# CN-Cape006-via08-fixed.net
KiCad netlist of a schematic drawn in EAGLE
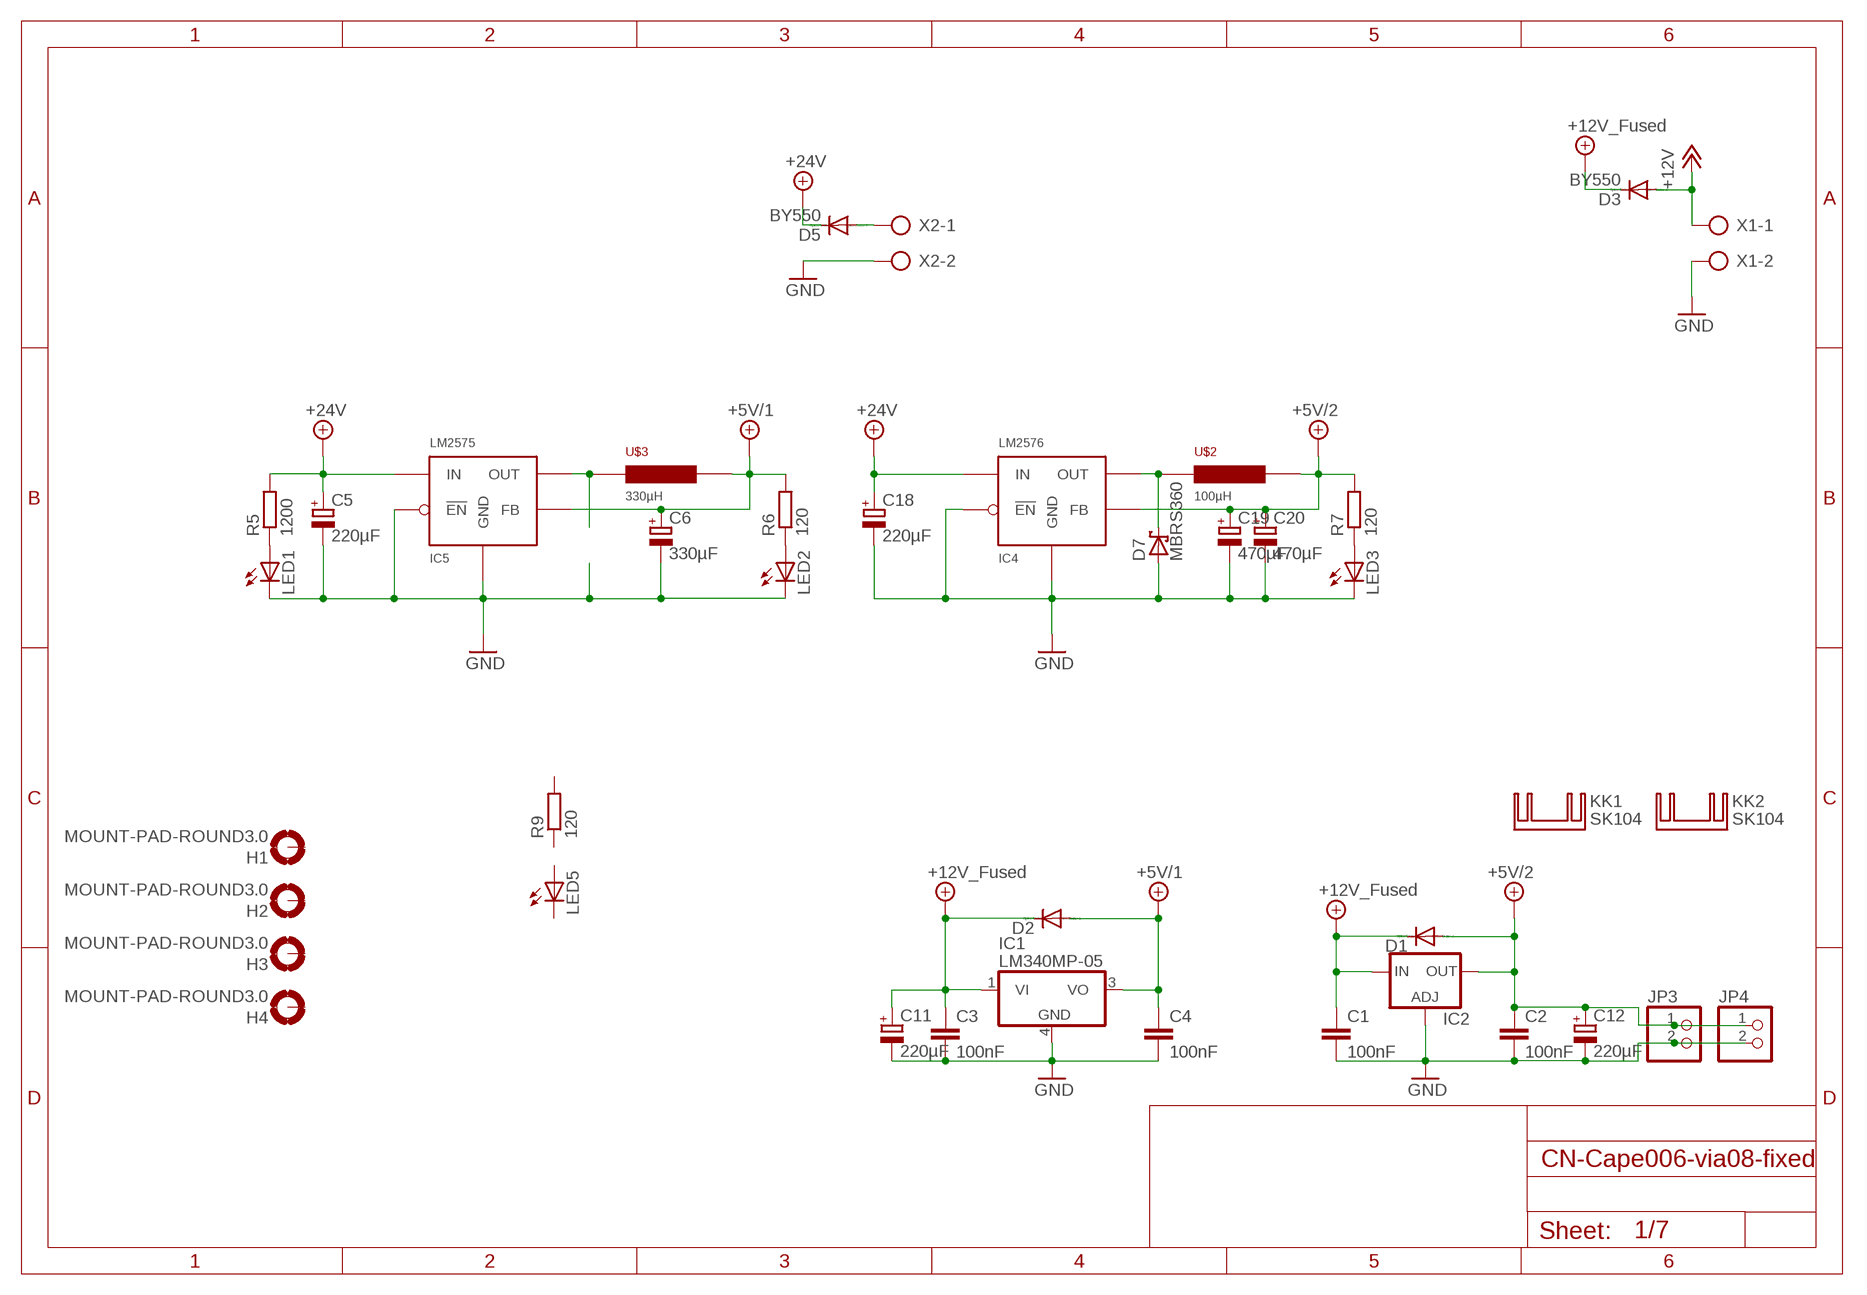
[diagram p0: schematic, sheet 1]
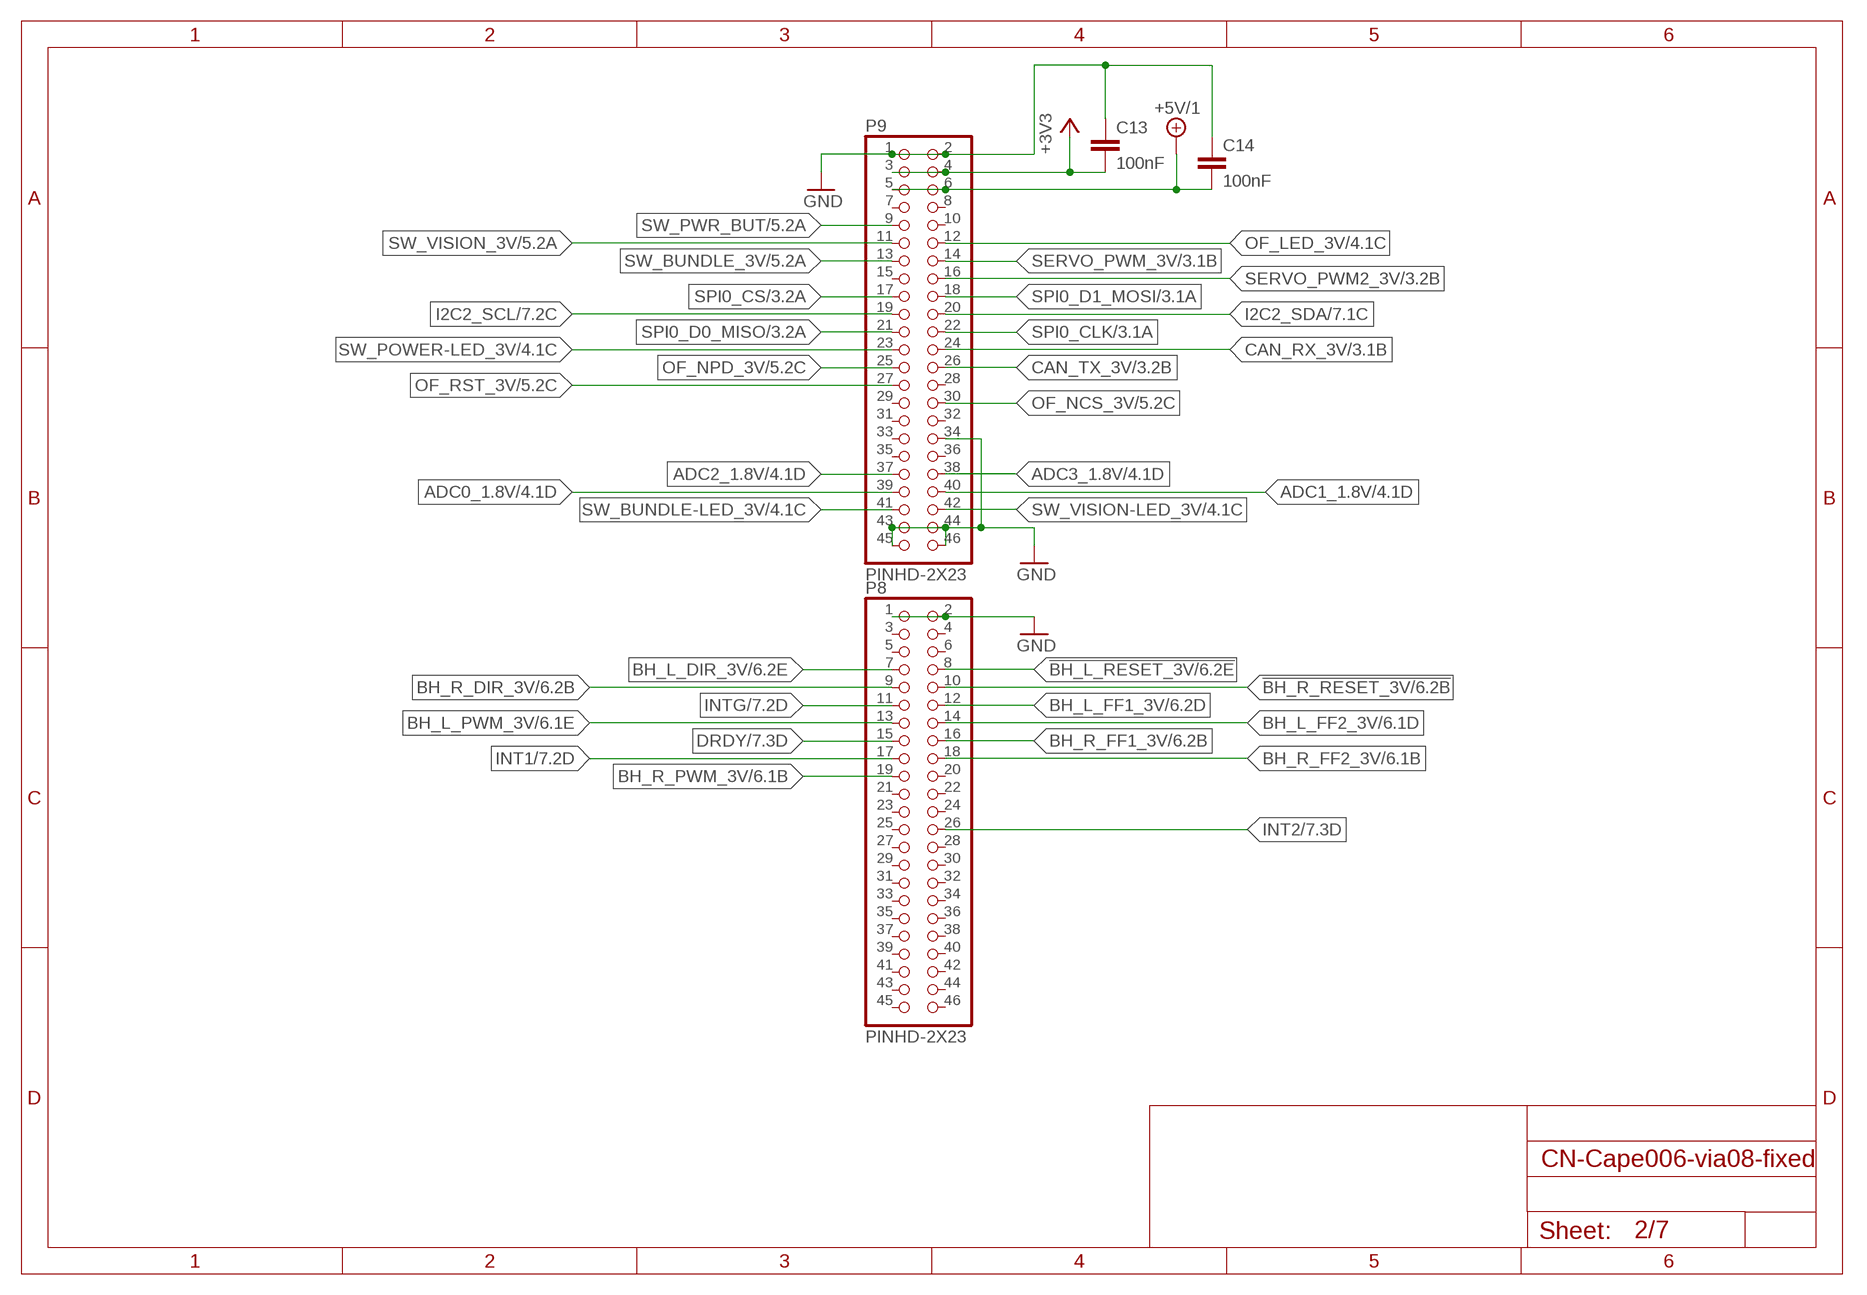
[diagram p1: schematic, sheet 2]
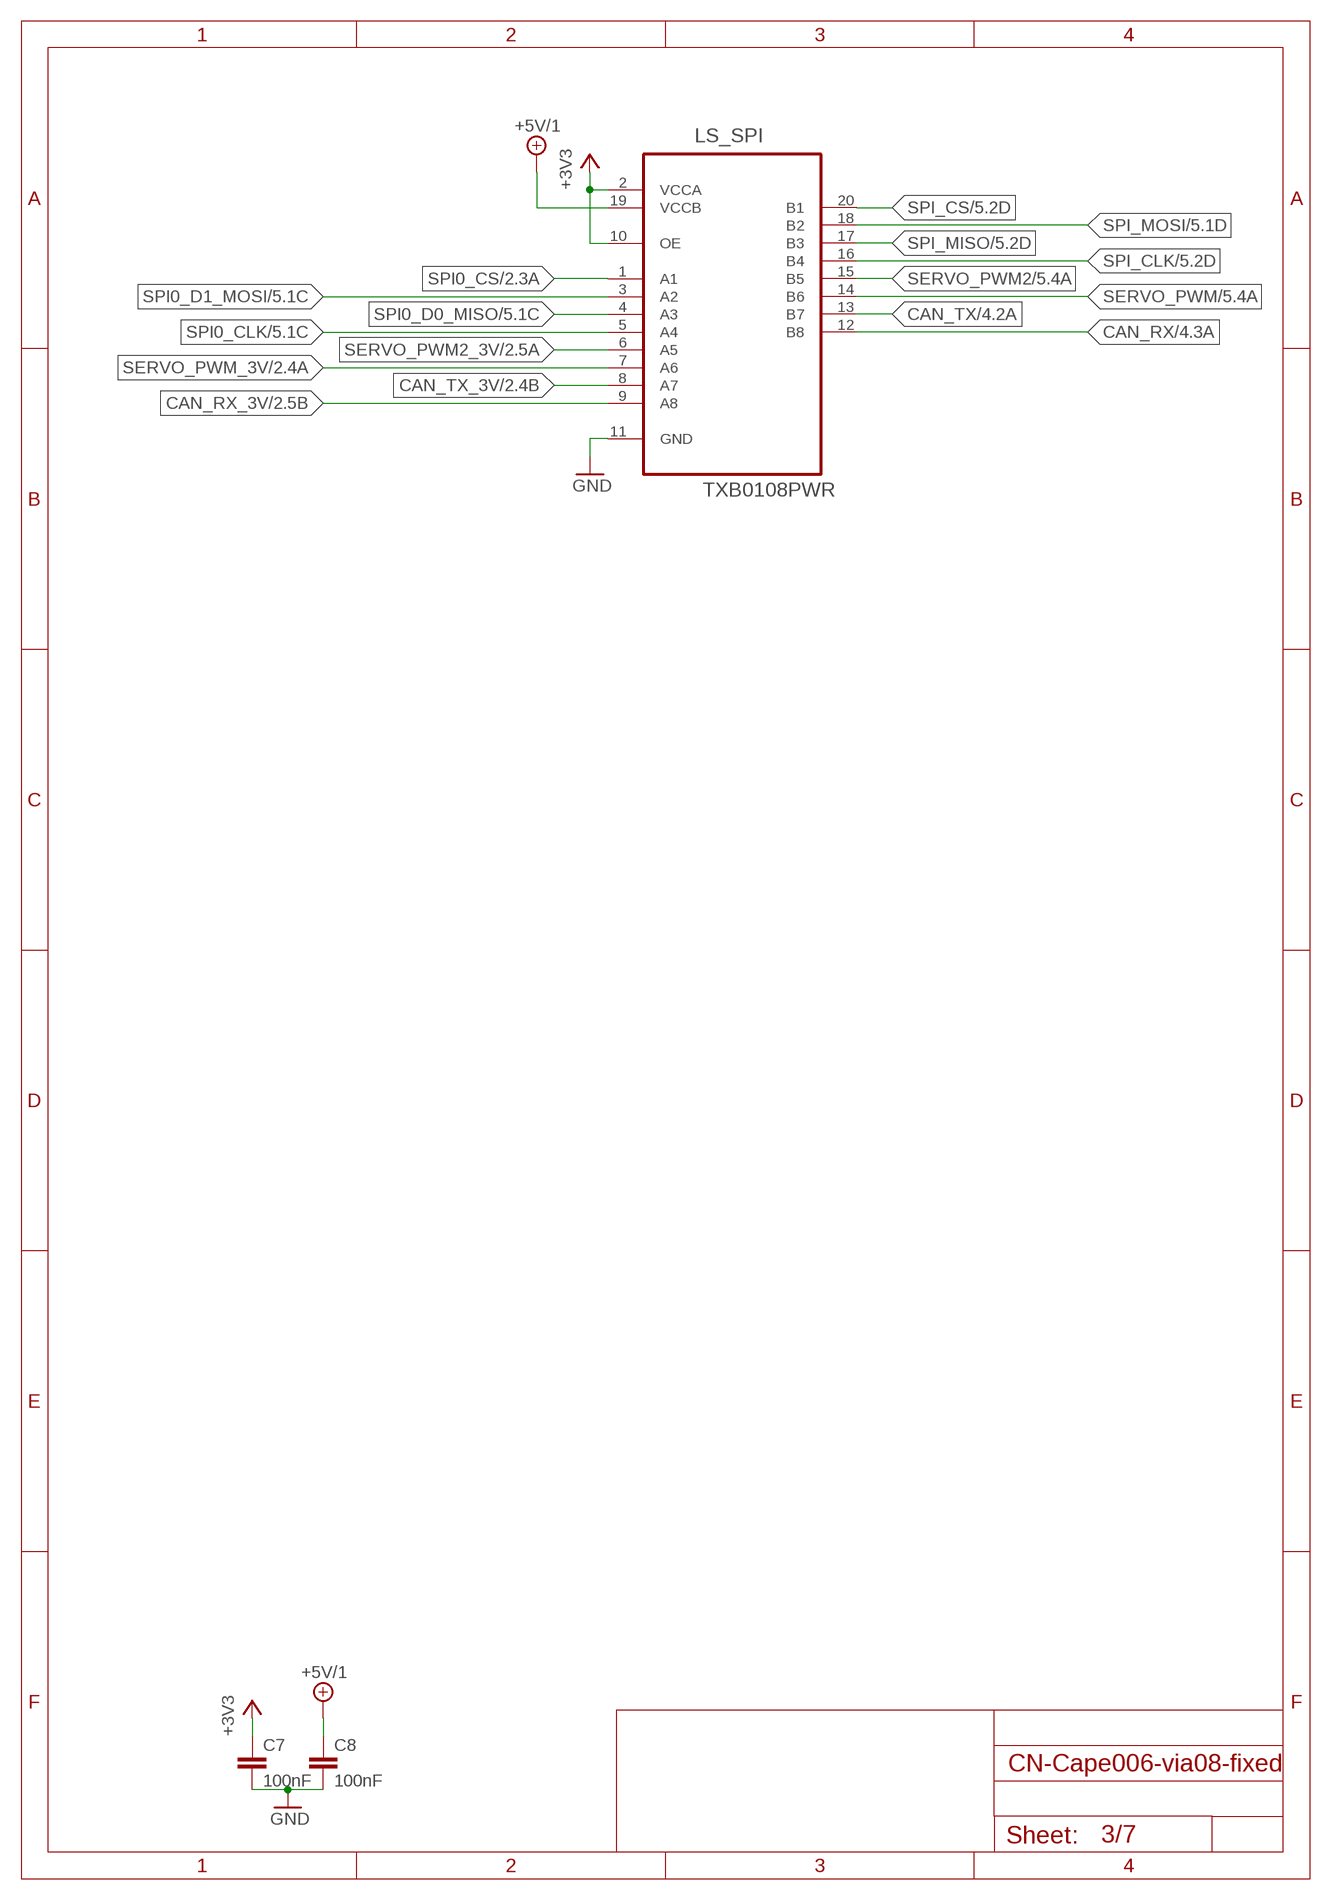
[diagram p2: schematic, sheet 3]
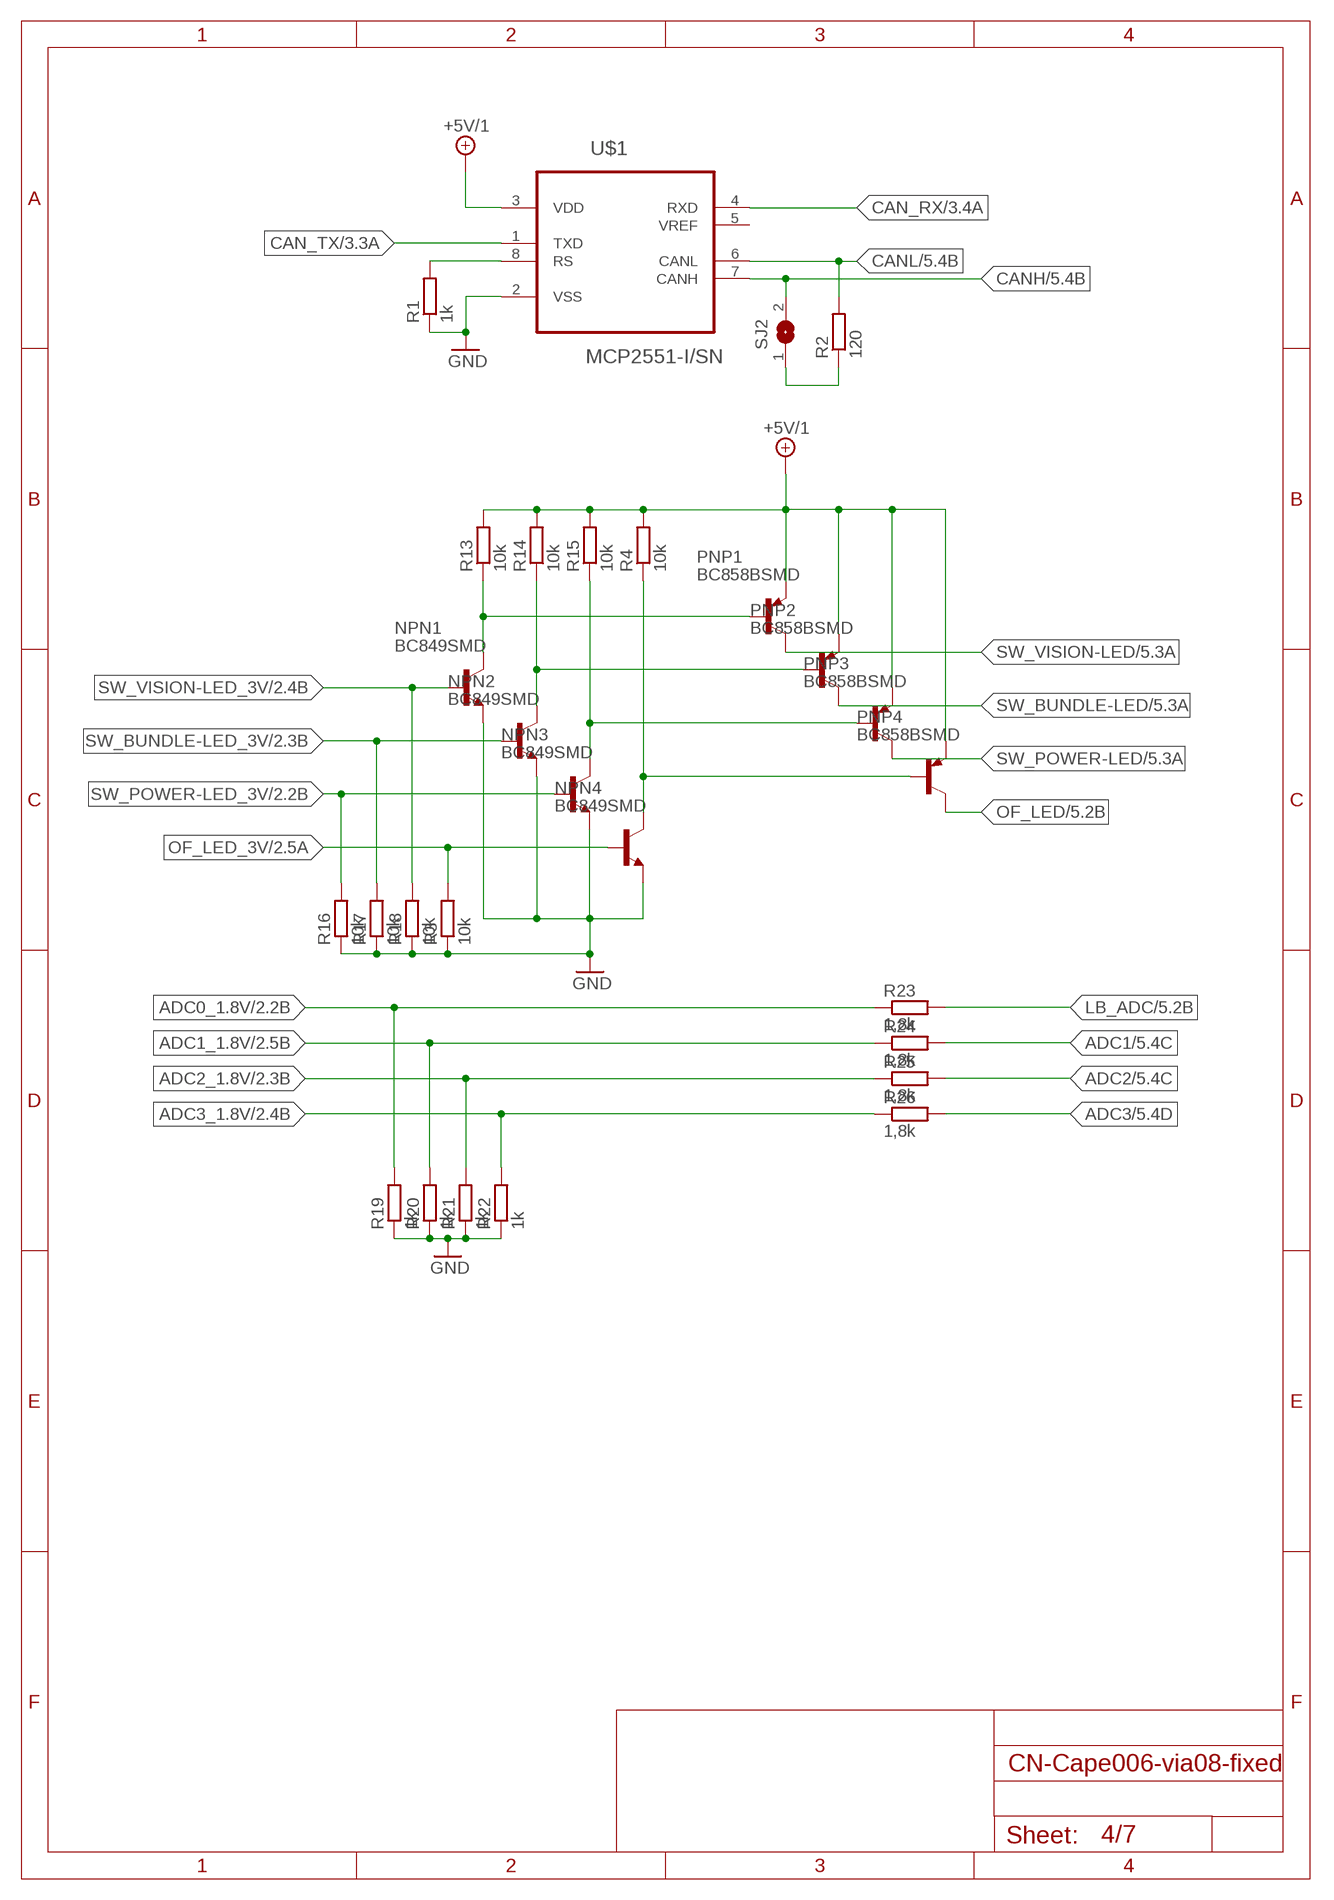
[diagram p3: schematic, sheet 4]
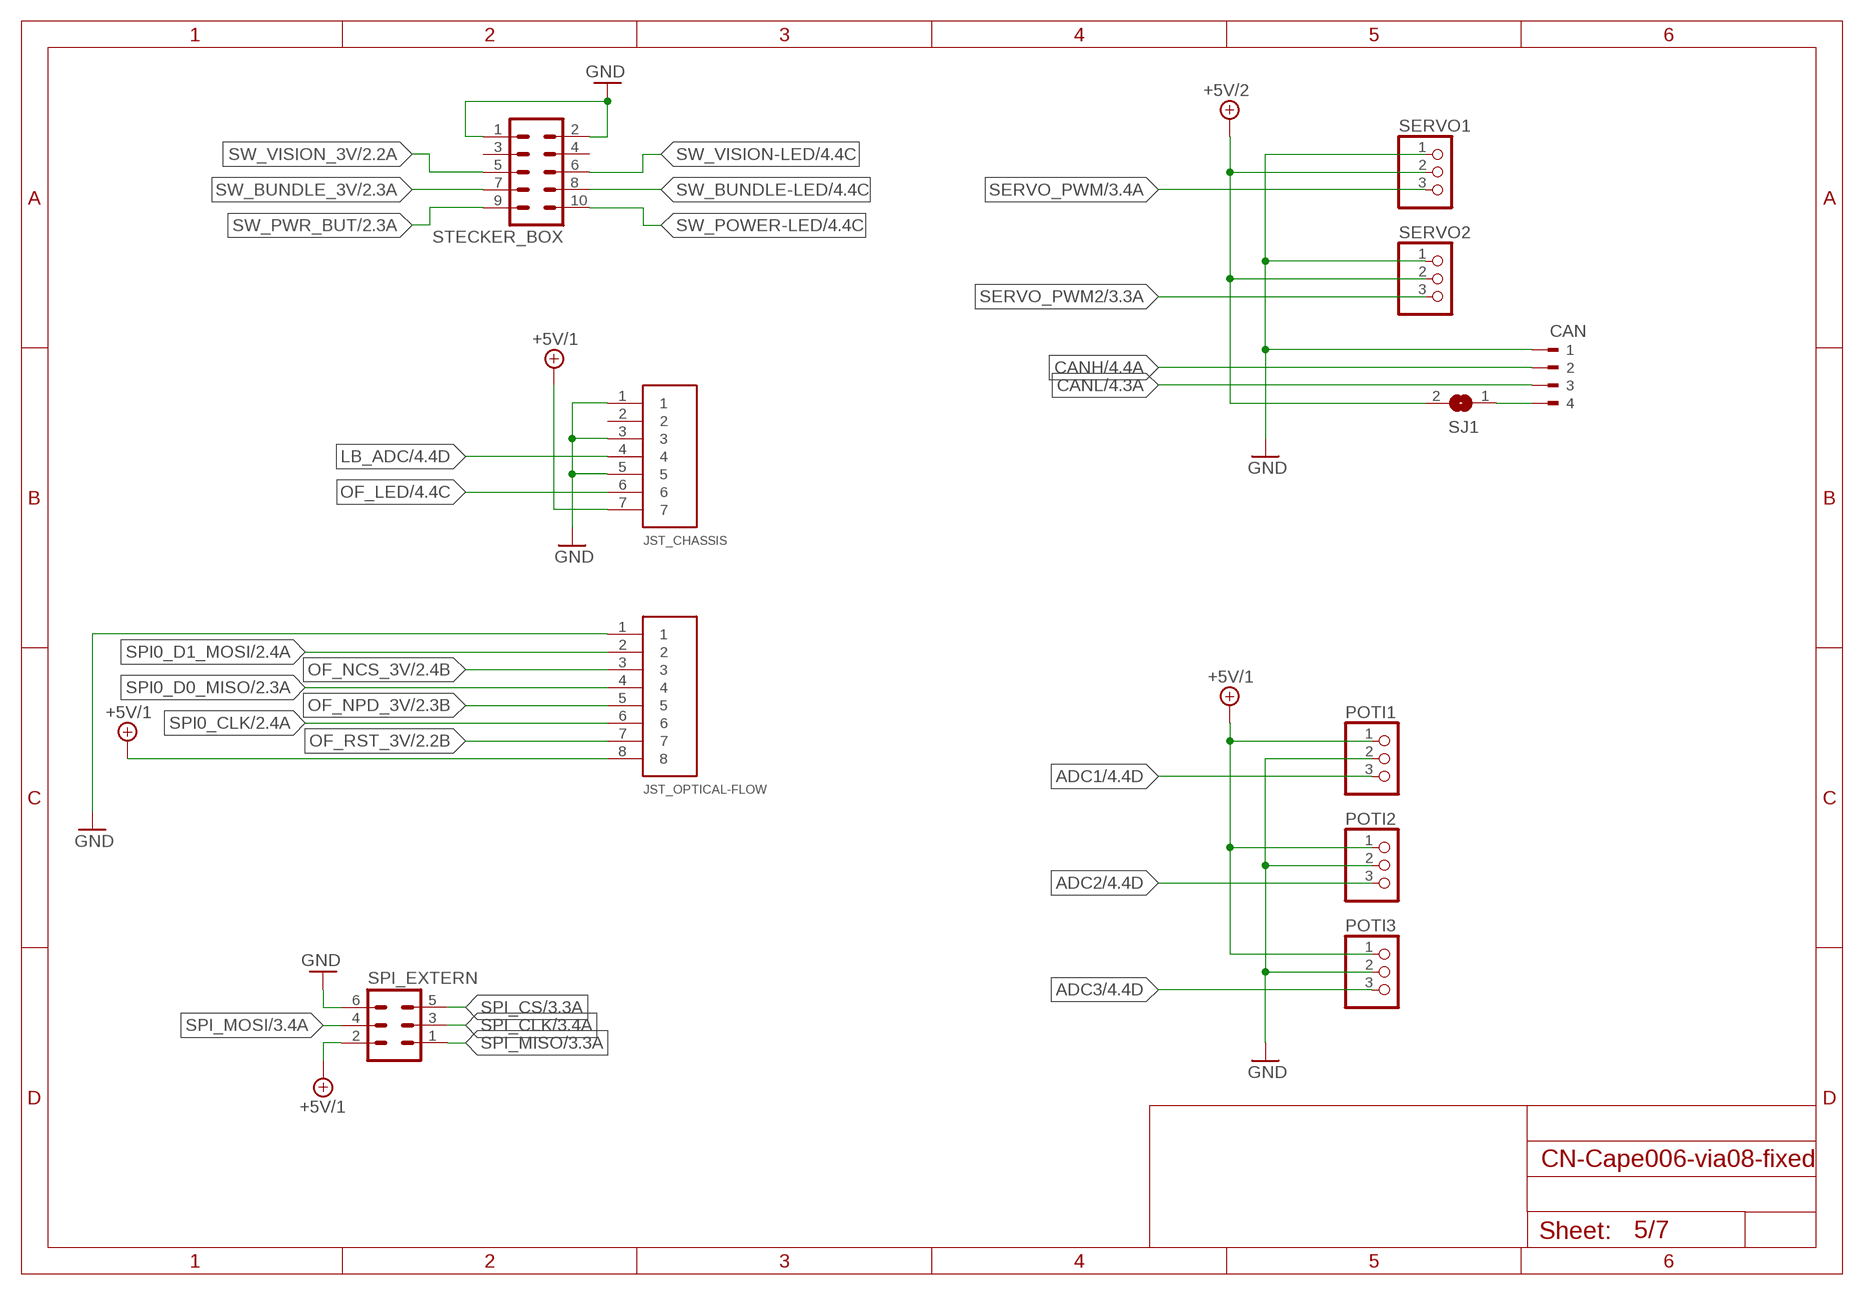
[diagram p4: schematic, sheet 5]
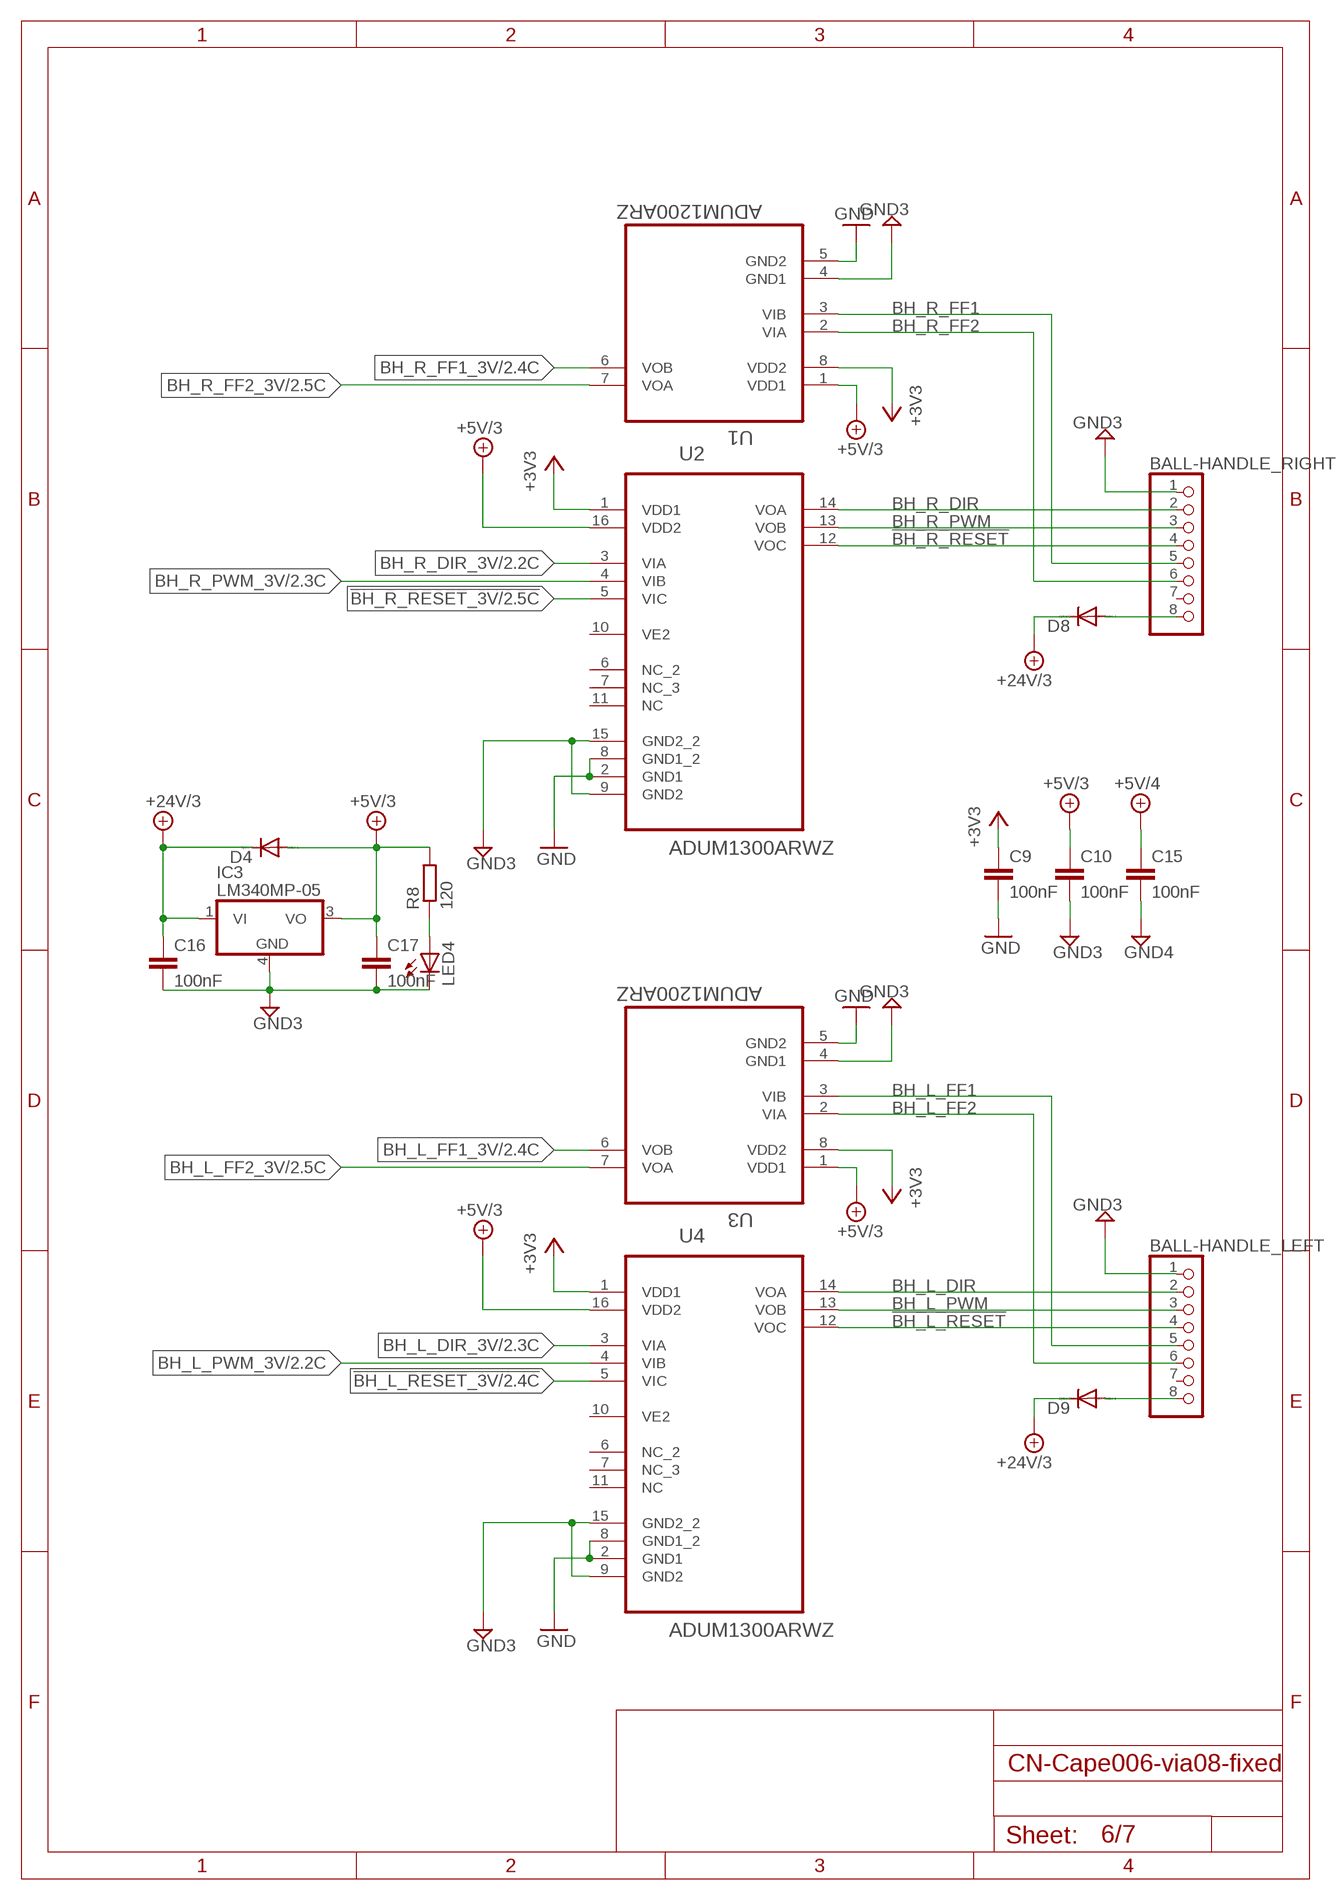
[diagram p5: schematic, sheet 6]
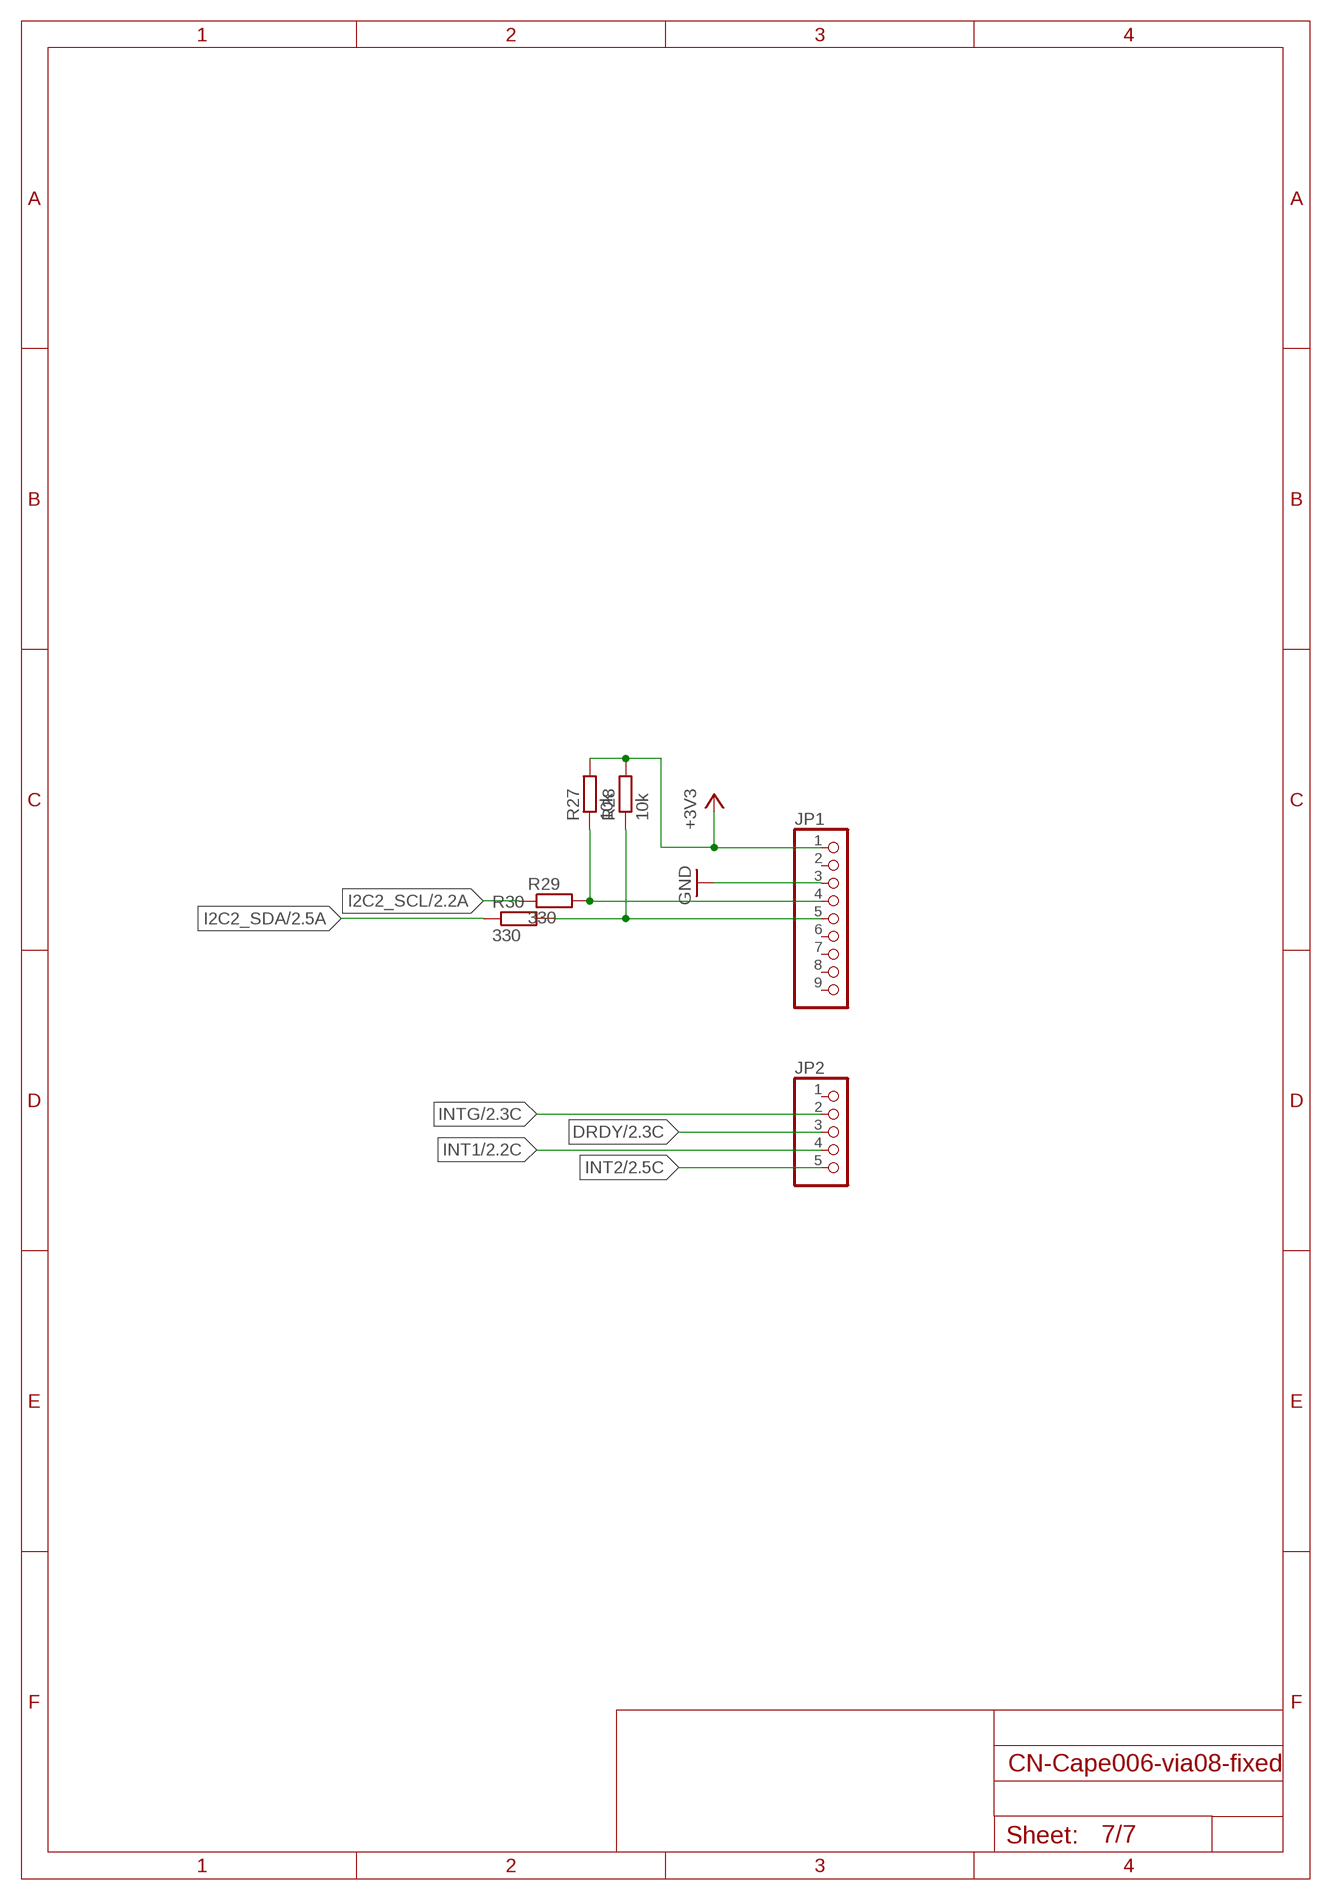
[diagram p6: schematic, sheet 7]

(export (version "E")
  (design (tool "Eeschema 10.0.6"))
  (components
    (comp (ref "JP1")
      (value "PINHD-1X9")
      (footprint "eagle-import:1X09")
      (libsource (lib "eagle-import") (part "PINHD-1X9"))
    )
    (comp (ref "JP2")
      (value "PINHD-1X5")
      (footprint "eagle-import:1X05")
      (libsource (lib "eagle-import") (part "PINHD-1X5"))
    )
    (comp (ref "R27")
      (value "10k")
      (footprint "eagle-import:R0805")
      (libsource (lib "eagle-import") (part "R-EU_R0805"))
    )
    (comp (ref "R28")
      (value "10k")
      (footprint "eagle-import:R0805")
      (libsource (lib "eagle-import") (part "R-EU_R0805"))
    )
    (comp (ref "R29")
      (value "330")
      (footprint "eagle-import:R0805")
      (libsource (lib "eagle-import") (part "R-EU_R0805"))
    )
    (comp (ref "R30")
      (value "330")
      (footprint "eagle-import:R0805")
      (libsource (lib "eagle-import") (part "R-EU_R0805"))
    )
    (comp (ref "C13")
      (value "100nF")
      (footprint "eagle-import:C0603")
      (libsource (lib "eagle-import") (part "C-EUC0603"))
    )
    (comp (ref "C14")
      (value "100nF")
      (footprint "eagle-import:C0603")
      (libsource (lib "eagle-import") (part "C-EUC0603"))
    )
    (comp (ref "P8")
      (value "PINHD-2X23")
      (footprint "eagle-import:2X23")
      (libsource (lib "eagle-import") (part "PINHD-2X23"))
    )
    (comp (ref "P9")
      (value "PINHD-2X23")
      (footprint "eagle-import:2X23")
      (libsource (lib "eagle-import") (part "PINHD-2X23"))
    )
    (comp (ref "C1")
      (value "100nF")
      (footprint "eagle-import:C0603")
      (libsource (lib "eagle-import") (part "C-EUC0603"))
    )
    (comp (ref "C2")
      (value "100nF")
      (footprint "eagle-import:C0603")
      (libsource (lib "eagle-import") (part "C-EUC0603"))
    )
    (comp (ref "C3")
      (value "100nF")
      (footprint "eagle-import:C0603")
      (libsource (lib "eagle-import") (part "C-EUC0603"))
    )
    (comp (ref "C4")
      (value "100nF")
      (footprint "eagle-import:C0603")
      (libsource (lib "eagle-import") (part "C-EUC0603"))
    )
    (comp (ref "C5")
      (value "220µF")
      (footprint "eagle-import:E3,5-8")
      (libsource (lib "eagle-import") (part "CPOL-EUE3.5-8"))
    )
    (comp (ref "C6")
      (value "330µF")
      (footprint "eagle-import:E5-10,5")
      (libsource (lib "eagle-import") (part "CPOL-EUE5-10.5"))
    )
    (comp (ref "C11")
      (value "220µF")
      (footprint "eagle-import:E3,5-8")
      (libsource (lib "eagle-import") (part "CPOL-EUE3.5-8"))
    )
    (comp (ref "C12")
      (value "220µF")
      (footprint "eagle-import:E3,5-8")
      (libsource (lib "eagle-import") (part "CPOL-EUE3.5-8"))
    )
    (comp (ref "C18")
      (value "220µF")
      (footprint "eagle-import:E3,5-8")
      (libsource (lib "eagle-import") (part "CPOL-EUE3.5-8"))
    )
    (comp (ref "C19")
      (value "470µF")
      (footprint "eagle-import:E3,5-8")
      (libsource (lib "eagle-import") (part "CPOL-EUE3.5-8"))
    )
    (comp (ref "C20")
      (value "470µF")
      (footprint "eagle-import:E3,5-8")
      (libsource (lib "eagle-import") (part "CPOL-EUE3.5-8"))
    )
    (comp (ref "D1")
      (value "DIODE-SOD123")
      (footprint "eagle-import:SOD123")
      (libsource (lib "eagle-import") (part "DIODE-SOD123"))
    )
    (comp (ref "D2")
      (value "DIODE-SOD123")
      (footprint "eagle-import:SOD123")
      (libsource (lib "eagle-import") (part "DIODE-SOD123"))
    )
    (comp (ref "D3")
      (value "BY550")
      (footprint "eagle-import:DO27-15")
      (libsource (lib "eagle-import") (part "BY550"))
    )
    (comp (ref "D5")
      (value "BY550")
      (footprint "eagle-import:DO27-15")
      (libsource (lib "eagle-import") (part "BY550"))
    )
    (comp (ref "D7")
      (value "MBRS360")
      (footprint "eagle-import:SMC")
      (libsource (lib "eagle-import") (part "MBRS30T34"))
    )
    (comp (ref "H1")
      (value "MOUNT-PAD-ROUND3.0")
      (footprint "eagle-import:3,0-PAD")
      (libsource (lib "eagle-import") (part "MOUNT-PAD-ROUND3.0"))
    )
    (comp (ref "H2")
      (value "MOUNT-PAD-ROUND3.0")
      (footprint "eagle-import:3,0-PAD")
      (libsource (lib "eagle-import") (part "MOUNT-PAD-ROUND3.0"))
    )
    (comp (ref "H3")
      (value "MOUNT-PAD-ROUND3.0")
      (footprint "eagle-import:3,0-PAD")
      (libsource (lib "eagle-import") (part "MOUNT-PAD-ROUND3.0"))
    )
    (comp (ref "H4")
      (value "MOUNT-PAD-ROUND3.0")
      (footprint "eagle-import:3,0-PAD")
      (libsource (lib "eagle-import") (part "MOUNT-PAD-ROUND3.0"))
    )
    (comp (ref "IC1")
      (value "LM340MP-05")
      (footprint "eagle-import:SOT223")
      (libsource (lib "eagle-import") (part "LM340?-MP05"))
    )
    (comp (ref "IC2")
      (value "LM138-TL")
      (footprint "eagle-import:TO220L1")
      (libsource (lib "eagle-import") (part "LM138-TL"))
    )
    (comp (ref "IC4")
      (value "LM2576")
      (footprint "eagle-import:TO-220-5_IN-LINE")
      (libsource (lib "eagle-import") (part "LM2576-T05A"))
    )
    (comp (ref "IC5")
      (value "LM2575")
      (footprint "eagle-import:TO-220-5_IN-LINE")
      (libsource (lib "eagle-import") (part "LM2576-T05A"))
    )
    (comp (ref "JP3")
      (value "PINHD-1X2")
      (footprint "eagle-import:1X02")
      (libsource (lib "eagle-import") (part "PINHD-1X2"))
    )
    (comp (ref "JP4")
      (value "PINHD-1X2")
      (footprint "eagle-import:1X02")
      (libsource (lib "eagle-import") (part "PINHD-1X2"))
    )
    (comp (ref "KK1")
      (value "SK104")
      (footprint "eagle-import:SK104")
      (libsource (lib "eagle-import") (part "SK104"))
    )
    (comp (ref "KK2")
      (value "SK104")
      (footprint "eagle-import:SK104")
      (libsource (lib "eagle-import") (part "SK104"))
    )
    (comp (ref "LED1")
      (value "LEDCHIP-LED0603")
      (footprint "eagle-import:CHIP-LED0603")
      (libsource (lib "eagle-import") (part "LEDCHIP-LED0603"))
    )
    (comp (ref "LED2")
      (value "LEDCHIP-LED0603")
      (footprint "eagle-import:CHIP-LED0603")
      (libsource (lib "eagle-import") (part "LEDCHIP-LED0603"))
    )
    (comp (ref "LED3")
      (value "LEDCHIP-LED0603")
      (footprint "eagle-import:CHIP-LED0603")
      (libsource (lib "eagle-import") (part "LEDCHIP-LED0603"))
    )
    (comp (ref "LED5")
      (value "LEDCHIP-LED0603")
      (footprint "eagle-import:CHIP-LED0603")
      (libsource (lib "eagle-import") (part "LEDCHIP-LED0603"))
    )
    (comp (ref "R5")
      (value "1200")
      (footprint "eagle-import:R0805")
      (libsource (lib "eagle-import") (part "R-EU_R0805"))
    )
    (comp (ref "R6")
      (value "120")
      (footprint "eagle-import:R0805")
      (libsource (lib "eagle-import") (part "R-EU_R0805"))
    )
    (comp (ref "R7")
      (value "120")
      (footprint "eagle-import:R0805")
      (libsource (lib "eagle-import") (part "R-EU_R0805"))
    )
    (comp (ref "R9")
      (value "120")
      (footprint "eagle-import:R0805")
      (libsource (lib "eagle-import") (part "R-EU_R0805"))
    )
    (comp (ref "U$2")
      (value "100µH")
      (footprint "eagle-import:PISR")
      (libsource (lib "eagle-import") (part "PISR"))
    )
    (comp (ref "U$3")
      (value "330µH")
      (footprint "eagle-import:PISR")
      (libsource (lib "eagle-import") (part "PISR"))
    )
    (comp (ref "X1")
      (value "AK500/2-H")
      (footprint "eagle-import:AK500_2-H")
      (libsource (lib "eagle-import") (part "AK500/2-H"))
    )
    (comp (ref "X2")
      (value "AK500/2-H")
      (footprint "eagle-import:AK500_2-H")
      (libsource (lib "eagle-import") (part "AK500/2-H"))
    )
    (comp (ref "NPN1")
      (value "BC849SMD")
      (footprint "eagle-import:SOT23-BEC")
      (libsource (lib "eagle-import") (part "BC849SMD"))
    )
    (comp (ref "NPN2")
      (value "BC849SMD")
      (footprint "eagle-import:SOT23-BEC")
      (libsource (lib "eagle-import") (part "BC849SMD"))
    )
    (comp (ref "NPN3")
      (value "BC849SMD")
      (footprint "eagle-import:SOT23-BEC")
      (libsource (lib "eagle-import") (part "BC849SMD"))
    )
    (comp (ref "NPN4")
      (value "BC849SMD")
      (footprint "eagle-import:SOT23-BEC")
      (libsource (lib "eagle-import") (part "BC849SMD"))
    )
    (comp (ref "PNP1")
      (value "BC858BSMD")
      (footprint "eagle-import:SOT23-BEC")
      (libsource (lib "eagle-import") (part "BC858SMDB"))
    )
    (comp (ref "PNP2")
      (value "BC858BSMD")
      (footprint "eagle-import:SOT23-BEC")
      (libsource (lib "eagle-import") (part "BC858SMDB"))
    )
    (comp (ref "PNP3")
      (value "BC858BSMD")
      (footprint "eagle-import:SOT23-BEC")
      (libsource (lib "eagle-import") (part "BC858SMDB"))
    )
    (comp (ref "PNP4")
      (value "BC858BSMD")
      (footprint "eagle-import:SOT23-BEC")
      (libsource (lib "eagle-import") (part "BC858SMDB"))
    )
    (comp (ref "R1")
      (value "1k")
      (footprint "eagle-import:R0805")
      (libsource (lib "eagle-import") (part "R-EU_R0805"))
    )
    (comp (ref "R2")
      (value "120")
      (footprint "eagle-import:R0805")
      (libsource (lib "eagle-import") (part "R-EU_R0805"))
    )
    (comp (ref "R3")
      (value "10k")
      (footprint "eagle-import:R0805")
      (libsource (lib "eagle-import") (part "R-EU_R0805"))
    )
    (comp (ref "R4")
      (value "10k")
      (footprint "eagle-import:R0805")
      (libsource (lib "eagle-import") (part "R-EU_R0805"))
    )
    (comp (ref "R13")
      (value "10k")
      (footprint "eagle-import:R0805")
      (libsource (lib "eagle-import") (part "R-EU_R0805"))
    )
    (comp (ref "R14")
      (value "10k")
      (footprint "eagle-import:R0805")
      (libsource (lib "eagle-import") (part "R-EU_R0805"))
    )
    (comp (ref "R15")
      (value "10k")
      (footprint "eagle-import:R0805")
      (libsource (lib "eagle-import") (part "R-EU_R0805"))
    )
    (comp (ref "R16")
      (value "10k")
      (footprint "eagle-import:R0805")
      (libsource (lib "eagle-import") (part "R-EU_R0805"))
    )
    (comp (ref "R17")
      (value "10k")
      (footprint "eagle-import:R0805")
      (libsource (lib "eagle-import") (part "R-EU_R0805"))
    )
    (comp (ref "R18")
      (value "10k")
      (footprint "eagle-import:R0805")
      (libsource (lib "eagle-import") (part "R-EU_R0805"))
    )
    (comp (ref "R19")
      (value "1k")
      (footprint "eagle-import:R0805")
      (libsource (lib "eagle-import") (part "R-EU_R0805"))
    )
    (comp (ref "R20")
      (value "1k")
      (footprint "eagle-import:R0805")
      (libsource (lib "eagle-import") (part "R-EU_R0805"))
    )
    (comp (ref "R21")
      (value "1k")
      (footprint "eagle-import:R0805")
      (libsource (lib "eagle-import") (part "R-EU_R0805"))
    )
    (comp (ref "R22")
      (value "1k")
      (footprint "eagle-import:R0805")
      (libsource (lib "eagle-import") (part "R-EU_R0805"))
    )
    (comp (ref "R23")
      (value "1,8k")
      (footprint "eagle-import:R0805")
      (libsource (lib "eagle-import") (part "R-EU_R0805"))
    )
    (comp (ref "R24")
      (value "1,8k")
      (footprint "eagle-import:R0805")
      (libsource (lib "eagle-import") (part "R-EU_R0805"))
    )
    (comp (ref "R25")
      (value "1,8k")
      (footprint "eagle-import:R0805")
      (libsource (lib "eagle-import") (part "R-EU_R0805"))
    )
    (comp (ref "R26")
      (value "1,8k")
      (footprint "eagle-import:R0805")
      (libsource (lib "eagle-import") (part "R-EU_R0805"))
    )
    (comp (ref "SJ2") (value "SJ") (footprint "eagle-import:SJ") (libsource (lib "eagle-import") (part "SJ")))
    (comp (ref "U$1")
      (value "MCP2551-I/SN")
      (footprint "eagle-import:SOIC127P600X175-8N")
      (libsource (lib "eagle-import") (part "MCP2551-I/SN"))
    )
    (comp (ref "CAN")
      (value "90-4")
      (footprint "eagle-import:90-4")
      (libsource (lib "eagle-import") (part "90-4"))
    )
    (comp (ref "JST_CHASSIS")
      (value "S7PIN")
      (footprint "eagle-import:S7B-EH")
      (libsource (lib "eagle-import") (part "S7PIN"))
    )
    (comp (ref "JST_OPTICAL-FLOW")
      (value "S8PIN")
      (footprint "eagle-import:S8B-EH")
      (libsource (lib "eagle-import") (part "S8PIN"))
    )
    (comp (ref "POTI1")
      (value "PINHD-1X3")
      (footprint "eagle-import:1X03")
      (libsource (lib "eagle-import") (part "PINHD-1X3"))
    )
    (comp (ref "POTI2")
      (value "PINHD-1X3")
      (footprint "eagle-import:1X03")
      (libsource (lib "eagle-import") (part "PINHD-1X3"))
    )
    (comp (ref "POTI3")
      (value "PINHD-1X3")
      (footprint "eagle-import:1X03")
      (libsource (lib "eagle-import") (part "PINHD-1X3"))
    )
    (comp (ref "SERVO1")
      (value "PINHD-1X3")
      (footprint "eagle-import:1X03")
      (libsource (lib "eagle-import") (part "PINHD-1X3"))
    )
    (comp (ref "SERVO2")
      (value "PINHD-1X3")
      (footprint "eagle-import:1X03")
      (libsource (lib "eagle-import") (part "PINHD-1X3"))
    )
    (comp (ref "SJ1") (value "SJ") (footprint "eagle-import:SJ") (libsource (lib "eagle-import") (part "SJ")))
    (comp (ref "SPI_EXTERN")
      (value "ML6")
      (footprint "eagle-import:ML6")
      (libsource (lib "eagle-import") (part "ML6"))
    )
    (comp (ref "STECKER_BOX")
      (value "ML10")
      (footprint "eagle-import:ML10")
      (libsource (lib "eagle-import") (part "ML10"))
    )
    (comp (ref "C7")
      (value "100nF")
      (footprint "eagle-import:C0603")
      (libsource (lib "eagle-import") (part "C-EUC0603"))
    )
    (comp (ref "C8")
      (value "100nF")
      (footprint "eagle-import:C0603")
      (libsource (lib "eagle-import") (part "C-EUC0603"))
    )
    (comp (ref "LS_SPI")
      (value "TXB0108PWR")
      (footprint "eagle-import:SOP65P640X120-20N")
      (libsource (lib "eagle-import") (part "TXB0108PWR"))
    )
    (comp (ref "BALL-HANDLE_LEFT")
      (value "PINHD-1X8")
      (footprint "eagle-import:1X08")
      (libsource (lib "eagle-import") (part "PINHD-1X8"))
    )
    (comp (ref "BALL-HANDLE_RIGHT")
      (value "PINHD-1X8")
      (footprint "eagle-import:1X08")
      (libsource (lib "eagle-import") (part "PINHD-1X8"))
    )
    (comp (ref "C9")
      (value "100nF")
      (footprint "eagle-import:C0603")
      (libsource (lib "eagle-import") (part "C-EUC0603"))
    )
    (comp (ref "C10")
      (value "100nF")
      (footprint "eagle-import:C0603")
      (libsource (lib "eagle-import") (part "C-EUC0603"))
    )
    (comp (ref "C15")
      (value "100nF")
      (footprint "eagle-import:C0603")
      (libsource (lib "eagle-import") (part "C-EUC0603"))
    )
    (comp (ref "C16")
      (value "100nF")
      (footprint "eagle-import:C0603")
      (libsource (lib "eagle-import") (part "C-EUC0603"))
    )
    (comp (ref "C17")
      (value "100nF")
      (footprint "eagle-import:C0603")
      (libsource (lib "eagle-import") (part "C-EUC0603"))
    )
    (comp (ref "D4")
      (value "DIODE-SOD123")
      (footprint "eagle-import:SOD123")
      (libsource (lib "eagle-import") (part "DIODE-SOD123"))
    )
    (comp (ref "D8")
      (value "DIODE-SOD123")
      (footprint "eagle-import:SOD123")
      (libsource (lib "eagle-import") (part "DIODE-SOD123"))
    )
    (comp (ref "D9")
      (value "DIODE-SOD123")
      (footprint "eagle-import:SOD123")
      (libsource (lib "eagle-import") (part "DIODE-SOD123"))
    )
    (comp (ref "IC3")
      (value "LM340MP-05")
      (footprint "eagle-import:SOT223")
      (libsource (lib "eagle-import") (part "LM340?-MP05"))
    )
    (comp (ref "LED4")
      (value "LEDCHIP-LED0603")
      (footprint "eagle-import:CHIP-LED0603")
      (libsource (lib "eagle-import") (part "LEDCHIP-LED0603"))
    )
    (comp (ref "R8")
      (value "120")
      (footprint "eagle-import:R0805")
      (libsource (lib "eagle-import") (part "R-EU_R0805"))
    )
    (comp (ref "U1")
      (value "ADUM1200ARZ")
      (footprint "eagle-import:SOIC127P600X175-8N")
      (libsource (lib "eagle-import") (part "ADUM1200ARZ"))
    )
    (comp (ref "U2")
      (value "ADUM1300ARWZ")
      (footprint "eagle-import:SOIC127P1032X265-16N")
      (libsource (lib "eagle-import") (part "ADUM1300ARWZ"))
    )
    (comp (ref "U3")
      (value "ADUM1200ARZ")
      (footprint "eagle-import:SOIC127P600X175-8N")
      (libsource (lib "eagle-import") (part "ADUM1200ARZ"))
    )
    (comp (ref "U4")
      (value "ADUM1300ARWZ")
      (footprint "eagle-import:SOIC127P1032X265-16N")
      (libsource (lib "eagle-import") (part "ADUM1300ARWZ"))
    )
  )
  (nets
    (net (code "1") (name "+3V3") (class "Default")
      (node (ref "C13") (pin "2") (pinfunction "2_2") (pintype "passive"))
      (node (ref "C7") (pin "1") (pinfunction "1_1") (pintype "passive"))
      (node (ref "C9") (pin "1") (pinfunction "1_1") (pintype "passive"))
      (node (ref "JP1") (pin "1") (pinfunction "1_1") (pintype "passive"))
      (node (ref "LS_SPI") (pin "10") (pinfunction "OE_10") (pintype "input"))
      (node (ref "LS_SPI") (pin "2") (pinfunction "VCCA_2") (pintype "power_in"))
      (node (ref "P9") (pin "3") (pinfunction "3_3") (pintype "passive"))
      (node (ref "P9") (pin "4") (pinfunction "4_4") (pintype "passive"))
      (node (ref "R27") (pin "2") (pinfunction "2_2") (pintype "passive"))
      (node (ref "R28") (pin "2") (pinfunction "2_2") (pintype "passive"))
      (node (ref "U1") (pin "8") (pinfunction "VDD2_8") (pintype "power_in"))
      (node (ref "U2") (pin "1") (pinfunction "VDD1_1") (pintype "power_in"))
      (node (ref "U3") (pin "8") (pinfunction "VDD2_8") (pintype "power_in"))
      (node (ref "U4") (pin "1") (pinfunction "VDD1_1") (pintype "power_in"))
    )
    (net (code "2") (name "+5V{slash}1") (class "Default")
      (node (ref "C14") (pin "2") (pinfunction "2_2") (pintype "passive"))
      (node (ref "C4") (pin "1") (pinfunction "1_1") (pintype "passive"))
      (node (ref "C6") (pin "+") (pinfunction "+_+") (pintype "passive"))
      (node (ref "C8") (pin "1") (pinfunction "1_1") (pintype "passive"))
      (node (ref "D2") (pin "A") (pinfunction "A_A") (pintype "passive"))
      (node (ref "IC1") (pin "3") (pinfunction "VO_3") (pintype "passive"))
      (node (ref "IC5") (pin "FB") (pinfunction "FB_FB") (pintype "input"))
      (node (ref "JST_CHASSIS") (pin "7") (pinfunction "7_7") (pintype "bidirectional"))
      (node (ref "JST_OPTICAL-FLOW") (pin "8") (pinfunction "8_8") (pintype "bidirectional"))
      (node (ref "LS_SPI") (pin "19") (pinfunction "VCCB_19") (pintype "power_in"))
      (node (ref "P9") (pin "5") (pinfunction "5_5") (pintype "passive"))
      (node (ref "P9") (pin "6") (pinfunction "6_6") (pintype "passive"))
      (node (ref "PNP1") (pin "E") (pinfunction "E_E") (pintype "passive"))
      (node (ref "PNP2") (pin "E") (pinfunction "E_E") (pintype "passive"))
      (node (ref "PNP3") (pin "E") (pinfunction "E_E") (pintype "passive"))
      (node (ref "PNP4") (pin "E") (pinfunction "E_E") (pintype "passive"))
      (node (ref "POTI1") (pin "1") (pinfunction "1_1") (pintype "passive"))
      (node (ref "POTI2") (pin "1") (pinfunction "1_1") (pintype "passive"))
      (node (ref "POTI3") (pin "1") (pinfunction "1_1") (pintype "passive"))
      (node (ref "R13") (pin "2") (pinfunction "2_2") (pintype "passive"))
      (node (ref "R14") (pin "2") (pinfunction "2_2") (pintype "passive"))
      (node (ref "R15") (pin "2") (pinfunction "2_2") (pintype "passive"))
      (node (ref "R4") (pin "2") (pinfunction "2_2") (pintype "passive"))
      (node (ref "R6") (pin "2") (pinfunction "2_2") (pintype "passive"))
      (node (ref "SPI_EXTERN") (pin "2") (pinfunction "2_2") (pintype "passive"))
      (node (ref "U$1") (pin "3") (pinfunction "VDD_3") (pintype "power_in"))
      (node (ref "U$3") (pin "P$2") (pinfunction "P$2_P$2") (pintype "bidirectional"))
    )
    (net (code "3") (name "+5V{slash}2") (class "Default")
      (node (ref "C12") (pin "+") (pinfunction "+_+") (pintype "passive"))
      (node (ref "C19") (pin "+") (pinfunction "+_+") (pintype "passive"))
      (node (ref "C2") (pin "1") (pinfunction "1_1") (pintype "passive"))
      (node (ref "C20") (pin "+") (pinfunction "+_+") (pintype "passive"))
      (node (ref "D1") (pin "A") (pinfunction "A_A") (pintype "passive"))
      (node (ref "IC2") (pin "2") (pinfunction "OUT_2") (pintype "passive"))
      (node (ref "IC4") (pin "FB") (pinfunction "FB_FB") (pintype "input"))
      (node (ref "JP3") (pin "1") (pinfunction "1_1") (pintype "passive"))
      (node (ref "JP4") (pin "1") (pinfunction "1_1") (pintype "passive"))
      (node (ref "R7") (pin "2") (pinfunction "2_2") (pintype "passive"))
      (node (ref "SERVO1") (pin "2") (pinfunction "2_2") (pintype "passive"))
      (node (ref "SERVO2") (pin "2") (pinfunction "2_2") (pintype "passive"))
      (node (ref "SJ1") (pin "2") (pinfunction "2_2") (pintype "passive"))
      (node (ref "U$2") (pin "P$2") (pinfunction "P$2_P$2") (pintype "bidirectional"))
    )
    (net (code "4") (name "+5V{slash}3") (class "Default")
      (node (ref "C10") (pin "1") (pinfunction "1_1") (pintype "passive"))
      (node (ref "C17") (pin "1") (pinfunction "1_1") (pintype "passive"))
      (node (ref "D4") (pin "A") (pinfunction "A_A") (pintype "passive"))
      (node (ref "IC3") (pin "3") (pinfunction "VO_3") (pintype "passive"))
      (node (ref "R8") (pin "2") (pinfunction "2_2") (pintype "passive"))
      (node (ref "U1") (pin "1") (pinfunction "VDD1_1") (pintype "power_in"))
      (node (ref "U2") (pin "16") (pinfunction "VDD2_16") (pintype "power_in"))
      (node (ref "U3") (pin "1") (pinfunction "VDD1_1") (pintype "power_in"))
      (node (ref "U4") (pin "16") (pinfunction "VDD2_16") (pintype "power_in"))
    )
    (net (code "5") (name "+5V{slash}4") (class "Default")
      (node (ref "C15") (pin "1") (pinfunction "1_1") (pintype "passive"))
    )
    (net (code "6") (name "+10V") (class "Default")
      (node (ref "C1") (pin "1") (pinfunction "1_1") (pintype "passive"))
      (node (ref "C11") (pin "+") (pinfunction "+_+") (pintype "passive"))
      (node (ref "C3") (pin "1") (pinfunction "1_1") (pintype "passive"))
      (node (ref "D1") (pin "C") (pinfunction "C_C") (pintype "passive"))
      (node (ref "D2") (pin "C") (pinfunction "C_C") (pintype "passive"))
      (node (ref "D3") (pin "C") (pinfunction "C_C") (pintype "passive"))
      (node (ref "IC1") (pin "1") (pinfunction "VI_1") (pintype "input"))
      (node (ref "IC2") (pin "3") (pinfunction "IN_3") (pintype "input"))
    )
    (net (code "7") (name "+12V") (class "Default")
      (node (ref "D3") (pin "A") (pinfunction "A_A") (pintype "passive"))
      (node (ref "X1") (pin "1") (pinfunction "KL_1") (pintype "passive"))
    )
    (net (code "8") (name "+24V") (class "Default")
      (node (ref "C18") (pin "+") (pinfunction "+_+") (pintype "passive"))
      (node (ref "C5") (pin "+") (pinfunction "+_+") (pintype "passive"))
      (node (ref "D5") (pin "C") (pinfunction "C_C") (pintype "passive"))
      (node (ref "IC4") (pin "IN") (pinfunction "IN_IN") (pintype "input"))
      (node (ref "IC5") (pin "IN") (pinfunction "IN_IN") (pintype "input"))
      (node (ref "R5") (pin "2") (pinfunction "2_2") (pintype "passive"))
    )
    (net (code "9") (name "+24V{slash}3") (class "Default")
      (node (ref "C16") (pin "1") (pinfunction "1_1") (pintype "passive"))
      (node (ref "D4") (pin "C") (pinfunction "C_C") (pintype "passive"))
      (node (ref "D8") (pin "C") (pinfunction "C_C") (pintype "passive"))
      (node (ref "D9") (pin "C") (pinfunction "C_C") (pintype "passive"))
      (node (ref "IC3") (pin "1") (pinfunction "VI_1") (pintype "input"))
    )
    (net (code "10") (name "ADC0_1.8V") (class "Default")
      (node (ref "P9") (pin "39") (pinfunction "39_39") (pintype "passive"))
      (node (ref "R19") (pin "2") (pinfunction "2_2") (pintype "passive"))
      (node (ref "R23") (pin "1") (pinfunction "1_1") (pintype "passive"))
    )
    (net (code "11") (name "ADC1") (class "Default")
      (node (ref "POTI1") (pin "3") (pinfunction "3_3") (pintype "passive"))
      (node (ref "R24") (pin "2") (pinfunction "2_2") (pintype "passive"))
    )
    (net (code "12") (name "ADC1_1.8V") (class "Default")
      (node (ref "P9") (pin "40") (pinfunction "40_40") (pintype "passive"))
      (node (ref "R20") (pin "2") (pinfunction "2_2") (pintype "passive"))
      (node (ref "R24") (pin "1") (pinfunction "1_1") (pintype "passive"))
    )
    (net (code "13") (name "ADC2") (class "Default")
      (node (ref "POTI2") (pin "3") (pinfunction "3_3") (pintype "passive"))
      (node (ref "R25") (pin "2") (pinfunction "2_2") (pintype "passive"))
    )
    (net (code "14") (name "ADC2_1.8V") (class "Default")
      (node (ref "P9") (pin "37") (pinfunction "37_37") (pintype "passive"))
      (node (ref "R21") (pin "2") (pinfunction "2_2") (pintype "passive"))
      (node (ref "R25") (pin "1") (pinfunction "1_1") (pintype "passive"))
    )
    (net (code "15") (name "ADC3") (class "Default")
      (node (ref "POTI3") (pin "3") (pinfunction "3_3") (pintype "passive"))
      (node (ref "R26") (pin "2") (pinfunction "2_2") (pintype "passive"))
    )
    (net (code "16") (name "ADC3_1.8V") (class "Default")
      (node (ref "P9") (pin "38") (pinfunction "38_38") (pintype "passive"))
      (node (ref "R22") (pin "2") (pinfunction "2_2") (pintype "passive"))
      (node (ref "R26") (pin "1") (pinfunction "1_1") (pintype "passive"))
    )
    (net (code "17") (name "BH_L_DIR") (class "Default")
      (node (ref "BALL-HANDLE_LEFT") (pin "2") (pinfunction "2_2") (pintype "passive"))
      (node (ref "U4") (pin "14") (pinfunction "VOA_14") (pintype "output"))
    )
    (net (code "18") (name "BH_L_DIR_3V") (class "Default")
      (node (ref "P8") (pin "7") (pinfunction "7_7") (pintype "passive"))
      (node (ref "U4") (pin "3") (pinfunction "VIA_3") (pintype "input"))
    )
    (net (code "19") (name "BH_L_FF1") (class "Default")
      (node (ref "BALL-HANDLE_LEFT") (pin "5") (pinfunction "5_5") (pintype "passive"))
      (node (ref "U3") (pin "3") (pinfunction "VIB_3") (pintype "input"))
    )
    (net (code "20") (name "BH_L_FF1_3V") (class "Default")
      (node (ref "P8") (pin "12") (pinfunction "12_12") (pintype "passive"))
      (node (ref "U3") (pin "6") (pinfunction "VOB_6") (pintype "output"))
    )
    (net (code "21") (name "BH_L_FF2") (class "Default")
      (node (ref "BALL-HANDLE_LEFT") (pin "6") (pinfunction "6_6") (pintype "passive"))
      (node (ref "U3") (pin "2") (pinfunction "VIA_2") (pintype "input"))
    )
    (net (code "22") (name "BH_L_FF2_3V") (class "Default")
      (node (ref "P8") (pin "14") (pinfunction "14_14") (pintype "passive"))
      (node (ref "U3") (pin "7") (pinfunction "VOA_7") (pintype "output"))
    )
    (net (code "23") (name "BH_L_PWM") (class "Default")
      (node (ref "BALL-HANDLE_LEFT") (pin "3") (pinfunction "3_3") (pintype "passive"))
      (node (ref "U4") (pin "13") (pinfunction "VOB_13") (pintype "output"))
    )
    (net (code "24") (name "BH_L_PWM_3V") (class "Default")
      (node (ref "P8") (pin "13") (pinfunction "13_13") (pintype "passive"))
      (node (ref "U4") (pin "4") (pinfunction "VIB_4") (pintype "input"))
    )
    (net (code "25") (name "BH_R_DIR") (class "Default")
      (node (ref "BALL-HANDLE_RIGHT") (pin "2") (pinfunction "2_2") (pintype "passive"))
      (node (ref "U2") (pin "14") (pinfunction "VOA_14") (pintype "output"))
    )
    (net (code "26") (name "BH_R_DIR_3V") (class "Default")
      (node (ref "P8") (pin "9") (pinfunction "9_9") (pintype "passive"))
      (node (ref "U2") (pin "3") (pinfunction "VIA_3") (pintype "input"))
    )
    (net (code "27") (name "BH_R_FF1") (class "Default")
      (node (ref "BALL-HANDLE_RIGHT") (pin "5") (pinfunction "5_5") (pintype "passive"))
      (node (ref "U1") (pin "3") (pinfunction "VIB_3") (pintype "input"))
    )
    (net (code "28") (name "BH_R_FF1_3V") (class "Default")
      (node (ref "P8") (pin "16") (pinfunction "16_16") (pintype "passive"))
      (node (ref "U1") (pin "6") (pinfunction "VOB_6") (pintype "output"))
    )
    (net (code "29") (name "BH_R_FF2") (class "Default")
      (node (ref "BALL-HANDLE_RIGHT") (pin "6") (pinfunction "6_6") (pintype "passive"))
      (node (ref "U1") (pin "2") (pinfunction "VIA_2") (pintype "input"))
    )
    (net (code "30") (name "BH_R_FF2_3V") (class "Default")
      (node (ref "P8") (pin "18") (pinfunction "18_18") (pintype "passive"))
      (node (ref "U1") (pin "7") (pinfunction "VOA_7") (pintype "output"))
    )
    (net (code "31") (name "BH_R_PWM") (class "Default")
      (node (ref "BALL-HANDLE_RIGHT") (pin "3") (pinfunction "3_3") (pintype "passive"))
      (node (ref "U2") (pin "13") (pinfunction "VOB_13") (pintype "output"))
    )
    (net (code "32") (name "BH_R_PWM_3V") (class "Default")
      (node (ref "P8") (pin "19") (pinfunction "19_19") (pintype "passive"))
      (node (ref "U2") (pin "4") (pinfunction "VIB_4") (pintype "input"))
    )
    (net (code "33") (name "CANH") (class "Default")
      (node (ref "CAN") (pin "2") (pinfunction "2_2") (pintype "passive"))
      (node (ref "SJ2") (pin "2") (pinfunction "2_2") (pintype "passive"))
      (node (ref "U$1") (pin "7") (pinfunction "CANH_7") (pintype "bidirectional"))
    )
    (net (code "34") (name "CANL") (class "Default")
      (node (ref "CAN") (pin "3") (pinfunction "3_3") (pintype "passive"))
      (node (ref "R2") (pin "2") (pinfunction "2_2") (pintype "passive"))
      (node (ref "U$1") (pin "6") (pinfunction "CANL_6") (pintype "bidirectional"))
    )
    (net (code "35") (name "CAN_RX") (class "Default")
      (node (ref "LS_SPI") (pin "12") (pinfunction "B8_12") (pintype "bidirectional"))
      (node (ref "U$1") (pin "4") (pinfunction "RXD_4") (pintype "output"))
    )
    (net (code "36") (name "CAN_RX_3V") (class "Default")
      (node (ref "LS_SPI") (pin "9") (pinfunction "A8_9") (pintype "bidirectional"))
      (node (ref "P9") (pin "24") (pinfunction "24_24") (pintype "passive"))
    )
    (net (code "37") (name "CAN_TX") (class "Default")
      (node (ref "LS_SPI") (pin "13") (pinfunction "B7_13") (pintype "bidirectional"))
      (node (ref "U$1") (pin "1") (pinfunction "TXD_1") (pintype "input"))
    )
    (net (code "38") (name "CAN_TX_3V") (class "Default")
      (node (ref "LS_SPI") (pin "8") (pinfunction "A7_8") (pintype "bidirectional"))
      (node (ref "P9") (pin "26") (pinfunction "26_26") (pintype "passive"))
    )
    (net (code "39") (name "DRDY") (class "Default")
      (node (ref "JP2") (pin "3") (pinfunction "3_3") (pintype "passive"))
      (node (ref "P8") (pin "15") (pinfunction "15_15") (pintype "passive"))
    )
    (net (code "40") (name "GND") (class "Default")
      (node (ref "C1") (pin "2") (pinfunction "2_2") (pintype "passive"))
      (node (ref "C11") (pin "-") (pinfunction "-_-") (pintype "passive"))
      (node (ref "C12") (pin "-") (pinfunction "-_-") (pintype "passive"))
      (node (ref "C13") (pin "1") (pinfunction "1_1") (pintype "passive"))
      (node (ref "C14") (pin "1") (pinfunction "1_1") (pintype "passive"))
      (node (ref "C18") (pin "-") (pinfunction "-_-") (pintype "passive"))
      (node (ref "C19") (pin "-") (pinfunction "-_-") (pintype "passive"))
      (node (ref "C2") (pin "2") (pinfunction "2_2") (pintype "passive"))
      (node (ref "C20") (pin "-") (pinfunction "-_-") (pintype "passive"))
      (node (ref "C3") (pin "2") (pinfunction "2_2") (pintype "passive"))
      (node (ref "C4") (pin "2") (pinfunction "2_2") (pintype "passive"))
      (node (ref "C5") (pin "-") (pinfunction "-_-") (pintype "passive"))
      (node (ref "C6") (pin "-") (pinfunction "-_-") (pintype "passive"))
      (node (ref "C7") (pin "2") (pinfunction "2_2") (pintype "passive"))
      (node (ref "C8") (pin "2") (pinfunction "2_2") (pintype "passive"))
      (node (ref "C9") (pin "2") (pinfunction "2_2") (pintype "passive"))
      (node (ref "CAN") (pin "1") (pinfunction "1_1") (pintype "passive"))
      (node (ref "D7") (pin "A") (pinfunction "A_A") (pintype "passive"))
      (node (ref "IC1") (pin "4") (pinfunction "GND_4") (pintype "passive"))
      (node (ref "IC2") (pin "1") (pinfunction "ADJ_1") (pintype "input"))
      (node (ref "IC4") (pin "!EN") (pinfunction "~{EN}_!EN") (pintype "input"))
      (node (ref "IC4") (pin "GND") (pinfunction "GND_GND") (pintype "power_in"))
      (node (ref "IC5") (pin "!EN") (pinfunction "~{EN}_!EN") (pintype "input"))
      (node (ref "IC5") (pin "GND") (pinfunction "GND_GND") (pintype "power_in"))
      (node (ref "JP1") (pin "3") (pinfunction "3_3") (pintype "passive"))
      (node (ref "JP3") (pin "2") (pinfunction "2_2") (pintype "passive"))
      (node (ref "JP4") (pin "2") (pinfunction "2_2") (pintype "passive"))
      (node (ref "JST_CHASSIS") (pin "1") (pinfunction "1_1") (pintype "bidirectional"))
      (node (ref "JST_CHASSIS") (pin "3") (pinfunction "3_3") (pintype "bidirectional"))
      (node (ref "JST_CHASSIS") (pin "5") (pinfunction "5_5") (pintype "bidirectional"))
      (node (ref "JST_OPTICAL-FLOW") (pin "1") (pinfunction "1_1") (pintype "bidirectional"))
      (node (ref "LED1") (pin "C") (pinfunction "C_C") (pintype "passive"))
      (node (ref "LED2") (pin "C") (pinfunction "C_C") (pintype "passive"))
      (node (ref "LED3") (pin "C") (pinfunction "C_C") (pintype "passive"))
      (node (ref "LS_SPI") (pin "11") (pinfunction "GND_11") (pintype "passive"))
      (node (ref "NPN1") (pin "E") (pinfunction "E_E") (pintype "passive"))
      (node (ref "NPN2") (pin "E") (pinfunction "E_E") (pintype "passive"))
      (node (ref "NPN3") (pin "E") (pinfunction "E_E") (pintype "passive"))
      (node (ref "NPN4") (pin "E") (pinfunction "E_E") (pintype "passive"))
      (node (ref "P8") (pin "1") (pinfunction "1_1") (pintype "passive"))
      (node (ref "P8") (pin "2") (pinfunction "2_2") (pintype "passive"))
      (node (ref "P9") (pin "1") (pinfunction "1_1") (pintype "passive"))
      (node (ref "P9") (pin "2") (pinfunction "2_2") (pintype "passive"))
      (node (ref "P9") (pin "34") (pinfunction "34_34") (pintype "passive"))
      (node (ref "P9") (pin "43") (pinfunction "43_43") (pintype "passive"))
      (node (ref "P9") (pin "44") (pinfunction "44_44") (pintype "passive"))
      (node (ref "P9") (pin "45") (pinfunction "45_45") (pintype "passive"))
      (node (ref "P9") (pin "46") (pinfunction "46_46") (pintype "passive"))
      (node (ref "POTI1") (pin "2") (pinfunction "2_2") (pintype "passive"))
      (node (ref "POTI2") (pin "2") (pinfunction "2_2") (pintype "passive"))
      (node (ref "POTI3") (pin "2") (pinfunction "2_2") (pintype "passive"))
      (node (ref "R1") (pin "1") (pinfunction "1_1") (pintype "passive"))
      (node (ref "R16") (pin "1") (pinfunction "1_1") (pintype "passive"))
      (node (ref "R17") (pin "1") (pinfunction "1_1") (pintype "passive"))
      (node (ref "R18") (pin "1") (pinfunction "1_1") (pintype "passive"))
      (node (ref "R19") (pin "1") (pinfunction "1_1") (pintype "passive"))
      (node (ref "R20") (pin "1") (pinfunction "1_1") (pintype "passive"))
      (node (ref "R21") (pin "1") (pinfunction "1_1") (pintype "passive"))
      (node (ref "R22") (pin "1") (pinfunction "1_1") (pintype "passive"))
      (node (ref "R3") (pin "1") (pinfunction "1_1") (pintype "passive"))
      (node (ref "SERVO1") (pin "1") (pinfunction "1_1") (pintype "passive"))
      (node (ref "SERVO2") (pin "1") (pinfunction "1_1") (pintype "passive"))
      (node (ref "SPI_EXTERN") (pin "6") (pinfunction "6_6") (pintype "passive"))
      (node (ref "STECKER_BOX") (pin "1") (pinfunction "1_1") (pintype "passive"))
      (node (ref "STECKER_BOX") (pin "2") (pinfunction "2_2") (pintype "passive"))
      (node (ref "U$1") (pin "2") (pinfunction "VSS_2") (pintype "passive"))
      (node (ref "U1") (pin "5") (pinfunction "GND2_5") (pintype "passive"))
      (node (ref "U2") (pin "2") (pinfunction "GND1_2") (pintype "passive"))
      (node (ref "U2") (pin "8") (pinfunction "GND1_2_8") (pintype "passive"))
      (node (ref "U3") (pin "5") (pinfunction "GND2_5") (pintype "passive"))
      (node (ref "U4") (pin "2") (pinfunction "GND1_2") (pintype "passive"))
      (node (ref "U4") (pin "8") (pinfunction "GND1_2_8") (pintype "passive"))
      (node (ref "X1") (pin "2") (pinfunction "KL_2") (pintype "passive"))
      (node (ref "X2") (pin "2") (pinfunction "KL_2") (pintype "passive"))
    )
    (net (code "41") (name "GND3") (class "Default")
      (node (ref "BALL-HANDLE_LEFT") (pin "1") (pinfunction "1_1") (pintype "passive"))
      (node (ref "BALL-HANDLE_RIGHT") (pin "1") (pinfunction "1_1") (pintype "passive"))
      (node (ref "C10") (pin "2") (pinfunction "2_2") (pintype "passive"))
      (node (ref "C16") (pin "2") (pinfunction "2_2") (pintype "passive"))
      (node (ref "C17") (pin "2") (pinfunction "2_2") (pintype "passive"))
      (node (ref "IC3") (pin "4") (pinfunction "GND_4") (pintype "passive"))
      (node (ref "LED4") (pin "C") (pinfunction "C_C") (pintype "passive"))
      (node (ref "U1") (pin "4") (pinfunction "GND1_4") (pintype "passive"))
      (node (ref "U2") (pin "15") (pinfunction "GND2_2_15") (pintype "passive"))
      (node (ref "U2") (pin "9") (pinfunction "GND2_9") (pintype "passive"))
      (node (ref "U3") (pin "4") (pinfunction "GND1_4") (pintype "passive"))
      (node (ref "U4") (pin "15") (pinfunction "GND2_2_15") (pintype "passive"))
      (node (ref "U4") (pin "9") (pinfunction "GND2_9") (pintype "passive"))
    )
    (net (code "42") (name "GND4") (class "Default")
      (node (ref "C15") (pin "2") (pinfunction "2_2") (pintype "passive"))
    )
    (net (code "43") (name "I2C2_SCL") (class "Default")
      (node (ref "P9") (pin "19") (pinfunction "19_19") (pintype "passive"))
      (node (ref "R29") (pin "1") (pinfunction "1_1") (pintype "passive"))
    )
    (net (code "44") (name "I2C2_SDA") (class "Default")
      (node (ref "P9") (pin "20") (pinfunction "20_20") (pintype "passive"))
      (node (ref "R30") (pin "1") (pinfunction "1_1") (pintype "passive"))
    )
    (net (code "45") (name "INT1") (class "Default")
      (node (ref "JP2") (pin "4") (pinfunction "4_4") (pintype "passive"))
      (node (ref "P8") (pin "17") (pinfunction "17_17") (pintype "passive"))
    )
    (net (code "46") (name "INT2") (class "Default")
      (node (ref "JP2") (pin "5") (pinfunction "5_5") (pintype "passive"))
      (node (ref "P8") (pin "26") (pinfunction "26_26") (pintype "passive"))
    )
    (net (code "47") (name "INTG") (class "Default")
      (node (ref "JP2") (pin "2") (pinfunction "2_2") (pintype "passive"))
      (node (ref "P8") (pin "11") (pinfunction "11_11") (pintype "passive"))
    )
    (net (code "48") (name "LB_ADC") (class "Default")
      (node (ref "JST_CHASSIS") (pin "4") (pinfunction "4_4") (pintype "bidirectional"))
      (node (ref "R23") (pin "2") (pinfunction "2_2") (pintype "passive"))
    )
    (net (code "49") (name "Net-(BALL-HANDLE_LEFT-Pad8)") (class "Default")
      (node (ref "BALL-HANDLE_LEFT") (pin "8") (pinfunction "8_8") (pintype "passive"))
      (node (ref "D9") (pin "A") (pinfunction "A_A") (pintype "passive"))
    )
    (net (code "50") (name "Net-(BALL-HANDLE_RIGHT-Pad8)") (class "Default")
      (node (ref "BALL-HANDLE_RIGHT") (pin "8") (pinfunction "8_8") (pintype "passive"))
      (node (ref "D8") (pin "A") (pinfunction "A_A") (pintype "passive"))
    )
    (net (code "51") (name "Net-(CAN-Pad4)") (class "Default")
      (node (ref "CAN") (pin "4") (pinfunction "4_4") (pintype "passive"))
      (node (ref "SJ1") (pin "1") (pinfunction "1_1") (pintype "passive"))
    )
    (net (code "52") (name "Net-(D7-PadC)") (class "Default")
      (node (ref "D7") (pin "C") (pinfunction "C_C") (pintype "passive"))
      (node (ref "IC4") (pin "OUT") (pinfunction "OUT_OUT") (pintype "output"))
      (node (ref "U$2") (pin "P$1") (pinfunction "P$1_P$1") (pintype "bidirectional"))
    )
    (net (code "53") (name "Net-(IC5-PadOUT)") (class "Default")
      (node (ref "IC5") (pin "OUT") (pinfunction "OUT_OUT") (pintype "output"))
      (node (ref "U$3") (pin "P$1") (pinfunction "P$1_P$1") (pintype "bidirectional"))
    )
    (net (code "54") (name "Net-(JP1-Pad4)") (class "Default")
      (node (ref "JP1") (pin "4") (pinfunction "4_4") (pintype "passive"))
      (node (ref "R27") (pin "1") (pinfunction "1_1") (pintype "passive"))
      (node (ref "R29") (pin "2") (pinfunction "2_2") (pintype "passive"))
    )
    (net (code "55") (name "Net-(JP1-Pad5)") (class "Default")
      (node (ref "JP1") (pin "5") (pinfunction "5_5") (pintype "passive"))
      (node (ref "R28") (pin "1") (pinfunction "1_1") (pintype "passive"))
      (node (ref "R30") (pin "2") (pinfunction "2_2") (pintype "passive"))
    )
    (net (code "56") (name "Net-(LED1-PadA)") (class "Default")
      (node (ref "LED1") (pin "A") (pinfunction "A_A") (pintype "passive"))
      (node (ref "R5") (pin "1") (pinfunction "1_1") (pintype "passive"))
    )
    (net (code "57") (name "Net-(LED2-PadA)") (class "Default")
      (node (ref "LED2") (pin "A") (pinfunction "A_A") (pintype "passive"))
      (node (ref "R6") (pin "1") (pinfunction "1_1") (pintype "passive"))
    )
    (net (code "58") (name "Net-(LED3-PadA)") (class "Default")
      (node (ref "LED3") (pin "A") (pinfunction "A_A") (pintype "passive"))
      (node (ref "R7") (pin "1") (pinfunction "1_1") (pintype "passive"))
    )
    (net (code "59") (name "Net-(LED4-PadA)") (class "Default")
      (node (ref "LED4") (pin "A") (pinfunction "A_A") (pintype "passive"))
      (node (ref "R8") (pin "1") (pinfunction "1_1") (pintype "passive"))
    )
    (net (code "60") (name "Net-(NPN1-PadC)") (class "Default")
      (node (ref "NPN1") (pin "C") (pinfunction "C_C") (pintype "passive"))
      (node (ref "PNP1") (pin "B") (pinfunction "B_B") (pintype "passive"))
      (node (ref "R13") (pin "1") (pinfunction "1_1") (pintype "passive"))
    )
    (net (code "61") (name "Net-(NPN2-PadC)") (class "Default")
      (node (ref "NPN2") (pin "C") (pinfunction "C_C") (pintype "passive"))
      (node (ref "PNP2") (pin "B") (pinfunction "B_B") (pintype "passive"))
      (node (ref "R14") (pin "1") (pinfunction "1_1") (pintype "passive"))
    )
    (net (code "62") (name "Net-(NPN3-PadC)") (class "Default")
      (node (ref "NPN3") (pin "C") (pinfunction "C_C") (pintype "passive"))
      (node (ref "PNP3") (pin "B") (pinfunction "B_B") (pintype "passive"))
      (node (ref "R15") (pin "1") (pinfunction "1_1") (pintype "passive"))
    )
    (net (code "63") (name "Net-(NPN4-PadC)") (class "Default")
      (node (ref "NPN4") (pin "C") (pinfunction "C_C") (pintype "passive"))
      (node (ref "PNP4") (pin "B") (pinfunction "B_B") (pintype "passive"))
      (node (ref "R4") (pin "1") (pinfunction "1_1") (pintype "passive"))
    )
    (net (code "64") (name "Net-(R2-Pad1)") (class "Default")
      (node (ref "R2") (pin "1") (pinfunction "1_1") (pintype "passive"))
      (node (ref "SJ2") (pin "1") (pinfunction "1_1") (pintype "passive"))
    )
    (net (code "65") (name "Net-(U$1-RS)") (class "Default")
      (node (ref "R1") (pin "2") (pinfunction "2_2") (pintype "passive"))
      (node (ref "U$1") (pin "8") (pinfunction "RS_8") (pintype "input"))
    )
    (net (code "66") (name "Net-(X2A-KL)") (class "Default")
      (node (ref "D5") (pin "A") (pinfunction "A_A") (pintype "passive"))
      (node (ref "X2") (pin "1") (pinfunction "KL_1") (pintype "passive"))
    )
    (net (code "67") (name "OF_LED") (class "Default")
      (node (ref "JST_CHASSIS") (pin "6") (pinfunction "6_6") (pintype "bidirectional"))
      (node (ref "PNP4") (pin "C") (pinfunction "C_C") (pintype "passive"))
    )
    (net (code "68") (name "OF_LED_3V") (class "Default")
      (node (ref "NPN4") (pin "B") (pinfunction "B_B") (pintype "passive"))
      (node (ref "P9") (pin "12") (pinfunction "12_12") (pintype "passive"))
      (node (ref "R3") (pin "2") (pinfunction "2_2") (pintype "passive"))
    )
    (net (code "69") (name "OF_NCS_3V") (class "Default")
      (node (ref "JST_OPTICAL-FLOW") (pin "3") (pinfunction "3_3") (pintype "bidirectional"))
      (node (ref "P9") (pin "30") (pinfunction "30_30") (pintype "passive"))
    )
    (net (code "70") (name "OF_NPD_3V") (class "Default")
      (node (ref "JST_OPTICAL-FLOW") (pin "5") (pinfunction "5_5") (pintype "bidirectional"))
      (node (ref "P9") (pin "25") (pinfunction "25_25") (pintype "passive"))
    )
    (net (code "71") (name "OF_RST_3V") (class "Default")
      (node (ref "JST_OPTICAL-FLOW") (pin "7") (pinfunction "7_7") (pintype "bidirectional"))
      (node (ref "P9") (pin "27") (pinfunction "27_27") (pintype "passive"))
    )
    (net (code "72") (name "SERVO_PWM") (class "Default")
      (node (ref "LS_SPI") (pin "14") (pinfunction "B6_14") (pintype "bidirectional"))
      (node (ref "SERVO1") (pin "3") (pinfunction "3_3") (pintype "passive"))
    )
    (net (code "73") (name "SERVO_PWM2") (class "Default")
      (node (ref "LS_SPI") (pin "15") (pinfunction "B5_15") (pintype "bidirectional"))
      (node (ref "SERVO2") (pin "3") (pinfunction "3_3") (pintype "passive"))
    )
    (net (code "74") (name "SERVO_PWM2_3V") (class "Default")
      (node (ref "LS_SPI") (pin "6") (pinfunction "A5_6") (pintype "bidirectional"))
      (node (ref "P9") (pin "16") (pinfunction "16_16") (pintype "passive"))
    )
    (net (code "75") (name "SERVO_PWM_3V") (class "Default")
      (node (ref "LS_SPI") (pin "7") (pinfunction "A6_7") (pintype "bidirectional"))
      (node (ref "P9") (pin "14") (pinfunction "14_14") (pintype "passive"))
    )
    (net (code "76") (name "SPI0_CLK") (class "Default")
      (node (ref "JST_OPTICAL-FLOW") (pin "6") (pinfunction "6_6") (pintype "bidirectional"))
      (node (ref "LS_SPI") (pin "5") (pinfunction "A4_5") (pintype "bidirectional"))
      (node (ref "P9") (pin "22") (pinfunction "22_22") (pintype "passive"))
    )
    (net (code "77") (name "SPI0_CS") (class "Default")
      (node (ref "LS_SPI") (pin "1") (pinfunction "A1_1") (pintype "bidirectional"))
      (node (ref "P9") (pin "17") (pinfunction "17_17") (pintype "passive"))
    )
    (net (code "78") (name "SPI0_D0_MISO") (class "Default")
      (node (ref "JST_OPTICAL-FLOW") (pin "4") (pinfunction "4_4") (pintype "bidirectional"))
      (node (ref "LS_SPI") (pin "4") (pinfunction "A3_4") (pintype "bidirectional"))
      (node (ref "P9") (pin "21") (pinfunction "21_21") (pintype "passive"))
    )
    (net (code "79") (name "SPI0_D1_MOSI") (class "Default")
      (node (ref "JST_OPTICAL-FLOW") (pin "2") (pinfunction "2_2") (pintype "bidirectional"))
      (node (ref "LS_SPI") (pin "3") (pinfunction "A2_3") (pintype "bidirectional"))
      (node (ref "P9") (pin "18") (pinfunction "18_18") (pintype "passive"))
    )
    (net (code "80") (name "SPI_CLK") (class "Default")
      (node (ref "LS_SPI") (pin "16") (pinfunction "B4_16") (pintype "bidirectional"))
      (node (ref "SPI_EXTERN") (pin "3") (pinfunction "3_3") (pintype "passive"))
    )
    (net (code "81") (name "SPI_CS") (class "Default")
      (node (ref "LS_SPI") (pin "20") (pinfunction "B1_20") (pintype "bidirectional"))
      (node (ref "SPI_EXTERN") (pin "5") (pinfunction "5_5") (pintype "passive"))
    )
    (net (code "82") (name "SPI_MISO") (class "Default")
      (node (ref "LS_SPI") (pin "17") (pinfunction "B3_17") (pintype "bidirectional"))
      (node (ref "SPI_EXTERN") (pin "1") (pinfunction "1_1") (pintype "passive"))
    )
    (net (code "83") (name "SPI_MOSI") (class "Default")
      (node (ref "LS_SPI") (pin "18") (pinfunction "B2_18") (pintype "bidirectional"))
      (node (ref "SPI_EXTERN") (pin "4") (pinfunction "4_4") (pintype "passive"))
    )
    (net (code "84") (name "SW_BUNDLE-LED") (class "Default")
      (node (ref "PNP2") (pin "C") (pinfunction "C_C") (pintype "passive"))
      (node (ref "STECKER_BOX") (pin "8") (pinfunction "8_8") (pintype "passive"))
    )
    (net (code "85") (name "SW_BUNDLE-LED_3V") (class "Default")
      (node (ref "NPN2") (pin "B") (pinfunction "B_B") (pintype "passive"))
      (node (ref "P9") (pin "41") (pinfunction "41_41") (pintype "passive"))
      (node (ref "R17") (pin "2") (pinfunction "2_2") (pintype "passive"))
    )
    (net (code "86") (name "SW_BUNDLE_3V") (class "Default")
      (node (ref "P9") (pin "13") (pinfunction "13_13") (pintype "passive"))
      (node (ref "STECKER_BOX") (pin "7") (pinfunction "7_7") (pintype "passive"))
    )
    (net (code "87") (name "SW_POWER-LED") (class "Default")
      (node (ref "PNP3") (pin "C") (pinfunction "C_C") (pintype "passive"))
      (node (ref "STECKER_BOX") (pin "10") (pinfunction "10_10") (pintype "passive"))
    )
    (net (code "88") (name "SW_POWER-LED_3V") (class "Default")
      (node (ref "NPN3") (pin "B") (pinfunction "B_B") (pintype "passive"))
      (node (ref "P9") (pin "23") (pinfunction "23_23") (pintype "passive"))
      (node (ref "R16") (pin "2") (pinfunction "2_2") (pintype "passive"))
    )
    (net (code "89") (name "SW_PWR_BUT") (class "Default")
      (node (ref "P9") (pin "9") (pinfunction "9_9") (pintype "passive"))
      (node (ref "STECKER_BOX") (pin "9") (pinfunction "9_9") (pintype "passive"))
    )
    (net (code "90") (name "SW_VISION-LED") (class "Default")
      (node (ref "PNP1") (pin "C") (pinfunction "C_C") (pintype "passive"))
      (node (ref "STECKER_BOX") (pin "6") (pinfunction "6_6") (pintype "passive"))
    )
    (net (code "91") (name "SW_VISION-LED_3V") (class "Default")
      (node (ref "NPN1") (pin "B") (pinfunction "B_B") (pintype "passive"))
      (node (ref "P9") (pin "42") (pinfunction "42_42") (pintype "passive"))
      (node (ref "R18") (pin "2") (pinfunction "2_2") (pintype "passive"))
    )
    (net (code "92") (name "SW_VISION_3V") (class "Default")
      (node (ref "P9") (pin "11") (pinfunction "11_11") (pintype "passive"))
      (node (ref "STECKER_BOX") (pin "5") (pinfunction "5_5") (pintype "passive"))
    )
    (net (code "93") (name "unconnected-(BALL-HANDLE_LEFT-Pad7)") (class "Default")
      (node (ref "BALL-HANDLE_LEFT") (pin "7") (pinfunction "7_7") (pintype "passive"))
    )
    (net (code "94") (name "unconnected-(BALL-HANDLE_RIGHT-Pad7)") (class "Default")
      (node (ref "BALL-HANDLE_RIGHT") (pin "7") (pinfunction "7_7") (pintype "passive"))
    )
    (net (code "95") (name "unconnected-(H1-MOUNT-PadB3,0)") (class "Default")
      (node (ref "H1") (pin "B3,0") (pinfunction "MOUNT_B3,0") (pintype "passive"))
    )
    (net (code "96") (name "unconnected-(H2-MOUNT-PadB3,0)") (class "Default")
      (node (ref "H2") (pin "B3,0") (pinfunction "MOUNT_B3,0") (pintype "passive"))
    )
    (net (code "97") (name "unconnected-(H3-MOUNT-PadB3,0)") (class "Default")
      (node (ref "H3") (pin "B3,0") (pinfunction "MOUNT_B3,0") (pintype "passive"))
    )
    (net (code "98") (name "unconnected-(H4-MOUNT-PadB3,0)") (class "Default")
      (node (ref "H4") (pin "B3,0") (pinfunction "MOUNT_B3,0") (pintype "passive"))
    )
    (net (code "99") (name "unconnected-(JP1-Pad2)") (class "Default")
      (node (ref "JP1") (pin "2") (pinfunction "2_2") (pintype "passive"))
    )
    (net (code "100") (name "unconnected-(JP1-Pad6)") (class "Default")
      (node (ref "JP1") (pin "6") (pinfunction "6_6") (pintype "passive"))
    )
    (net (code "101") (name "unconnected-(JP1-Pad7)") (class "Default")
      (node (ref "JP1") (pin "7") (pinfunction "7_7") (pintype "passive"))
    )
    (net (code "102") (name "unconnected-(JP1-Pad8)") (class "Default")
      (node (ref "JP1") (pin "8") (pinfunction "8_8") (pintype "passive"))
    )
    (net (code "103") (name "unconnected-(JP1-Pad9)") (class "Default")
      (node (ref "JP1") (pin "9") (pinfunction "9_9") (pintype "passive"))
    )
    (net (code "104") (name "unconnected-(JP2-Pad1)") (class "Default")
      (node (ref "JP2") (pin "1") (pinfunction "1_1") (pintype "passive"))
    )
    (net (code "105") (name "unconnected-(JST_CHASSIS-Pad2)") (class "Default")
      (node (ref "JST_CHASSIS") (pin "2") (pinfunction "2_2") (pintype "bidirectional"))
    )
    (net (code "106") (name "unconnected-(LED5-PadA)") (class "Default")
      (node (ref "LED5") (pin "A") (pinfunction "A_A") (pintype "passive"))
    )
    (net (code "107") (name "unconnected-(LED5-PadC)") (class "Default")
      (node (ref "LED5") (pin "C") (pinfunction "C_C") (pintype "passive"))
    )
    (net (code "108") (name "unconnected-(P8-Pad3)") (class "Default")
      (node (ref "P8") (pin "3") (pinfunction "3_3") (pintype "passive"))
    )
    (net (code "109") (name "unconnected-(P8-Pad4)") (class "Default")
      (node (ref "P8") (pin "4") (pinfunction "4_4") (pintype "passive"))
    )
    (net (code "110") (name "unconnected-(P8-Pad5)") (class "Default")
      (node (ref "P8") (pin "5") (pinfunction "5_5") (pintype "passive"))
    )
    (net (code "111") (name "unconnected-(P8-Pad6)") (class "Default")
      (node (ref "P8") (pin "6") (pinfunction "6_6") (pintype "passive"))
    )
    (net (code "112") (name "unconnected-(P8-Pad20)") (class "Default")
      (node (ref "P8") (pin "20") (pinfunction "20_20") (pintype "passive"))
    )
    (net (code "113") (name "unconnected-(P8-Pad21)") (class "Default")
      (node (ref "P8") (pin "21") (pinfunction "21_21") (pintype "passive"))
    )
    (net (code "114") (name "unconnected-(P8-Pad22)") (class "Default")
      (node (ref "P8") (pin "22") (pinfunction "22_22") (pintype "passive"))
    )
    (net (code "115") (name "unconnected-(P8-Pad23)") (class "Default")
      (node (ref "P8") (pin "23") (pinfunction "23_23") (pintype "passive"))
    )
    (net (code "116") (name "unconnected-(P8-Pad24)") (class "Default")
      (node (ref "P8") (pin "24") (pinfunction "24_24") (pintype "passive"))
    )
    (net (code "117") (name "unconnected-(P8-Pad25)") (class "Default")
      (node (ref "P8") (pin "25") (pinfunction "25_25") (pintype "passive"))
    )
    (net (code "118") (name "unconnected-(P8-Pad27)") (class "Default")
      (node (ref "P8") (pin "27") (pinfunction "27_27") (pintype "passive"))
    )
    (net (code "119") (name "unconnected-(P8-Pad28)") (class "Default")
      (node (ref "P8") (pin "28") (pinfunction "28_28") (pintype "passive"))
    )
    (net (code "120") (name "unconnected-(P8-Pad29)") (class "Default")
      (node (ref "P8") (pin "29") (pinfunction "29_29") (pintype "passive"))
    )
    (net (code "121") (name "unconnected-(P8-Pad30)") (class "Default")
      (node (ref "P8") (pin "30") (pinfunction "30_30") (pintype "passive"))
    )
    (net (code "122") (name "unconnected-(P8-Pad31)") (class "Default")
      (node (ref "P8") (pin "31") (pinfunction "31_31") (pintype "passive"))
    )
    (net (code "123") (name "unconnected-(P8-Pad32)") (class "Default")
      (node (ref "P8") (pin "32") (pinfunction "32_32") (pintype "passive"))
    )
    (net (code "124") (name "unconnected-(P8-Pad33)") (class "Default")
      (node (ref "P8") (pin "33") (pinfunction "33_33") (pintype "passive"))
    )
    (net (code "125") (name "unconnected-(P8-Pad34)") (class "Default")
      (node (ref "P8") (pin "34") (pinfunction "34_34") (pintype "passive"))
    )
    (net (code "126") (name "unconnected-(P8-Pad35)") (class "Default")
      (node (ref "P8") (pin "35") (pinfunction "35_35") (pintype "passive"))
    )
    (net (code "127") (name "unconnected-(P8-Pad36)") (class "Default")
      (node (ref "P8") (pin "36") (pinfunction "36_36") (pintype "passive"))
    )
    (net (code "128") (name "unconnected-(P8-Pad37)") (class "Default")
      (node (ref "P8") (pin "37") (pinfunction "37_37") (pintype "passive"))
    )
    (net (code "129") (name "unconnected-(P8-Pad38)") (class "Default")
      (node (ref "P8") (pin "38") (pinfunction "38_38") (pintype "passive"))
    )
    (net (code "130") (name "unconnected-(P8-Pad39)") (class "Default")
      (node (ref "P8") (pin "39") (pinfunction "39_39") (pintype "passive"))
    )
    (net (code "131") (name "unconnected-(P8-Pad40)") (class "Default")
      (node (ref "P8") (pin "40") (pinfunction "40_40") (pintype "passive"))
    )
    (net (code "132") (name "unconnected-(P8-Pad41)") (class "Default")
      (node (ref "P8") (pin "41") (pinfunction "41_41") (pintype "passive"))
    )
    (net (code "133") (name "unconnected-(P8-Pad42)") (class "Default")
      (node (ref "P8") (pin "42") (pinfunction "42_42") (pintype "passive"))
    )
    (net (code "134") (name "unconnected-(P8-Pad43)") (class "Default")
      (node (ref "P8") (pin "43") (pinfunction "43_43") (pintype "passive"))
    )
    (net (code "135") (name "unconnected-(P8-Pad44)") (class "Default")
      (node (ref "P8") (pin "44") (pinfunction "44_44") (pintype "passive"))
    )
    (net (code "136") (name "unconnected-(P8-Pad45)") (class "Default")
      (node (ref "P8") (pin "45") (pinfunction "45_45") (pintype "passive"))
    )
    (net (code "137") (name "unconnected-(P8-Pad46)") (class "Default")
      (node (ref "P8") (pin "46") (pinfunction "46_46") (pintype "passive"))
    )
    (net (code "138") (name "unconnected-(P9-Pad7)") (class "Default")
      (node (ref "P9") (pin "7") (pinfunction "7_7") (pintype "passive"))
    )
    (net (code "139") (name "unconnected-(P9-Pad8)") (class "Default")
      (node (ref "P9") (pin "8") (pinfunction "8_8") (pintype "passive"))
    )
    (net (code "140") (name "unconnected-(P9-Pad10)") (class "Default")
      (node (ref "P9") (pin "10") (pinfunction "10_10") (pintype "passive"))
    )
    (net (code "141") (name "unconnected-(P9-Pad15)") (class "Default")
      (node (ref "P9") (pin "15") (pinfunction "15_15") (pintype "passive"))
    )
    (net (code "142") (name "unconnected-(P9-Pad28)") (class "Default")
      (node (ref "P9") (pin "28") (pinfunction "28_28") (pintype "passive"))
    )
    (net (code "143") (name "unconnected-(P9-Pad29)") (class "Default")
      (node (ref "P9") (pin "29") (pinfunction "29_29") (pintype "passive"))
    )
    (net (code "144") (name "unconnected-(P9-Pad31)") (class "Default")
      (node (ref "P9") (pin "31") (pinfunction "31_31") (pintype "passive"))
    )
    (net (code "145") (name "unconnected-(P9-Pad32)") (class "Default")
      (node (ref "P9") (pin "32") (pinfunction "32_32") (pintype "passive"))
    )
    (net (code "146") (name "unconnected-(P9-Pad33)") (class "Default")
      (node (ref "P9") (pin "33") (pinfunction "33_33") (pintype "passive"))
    )
    (net (code "147") (name "unconnected-(P9-Pad35)") (class "Default")
      (node (ref "P9") (pin "35") (pinfunction "35_35") (pintype "passive"))
    )
    (net (code "148") (name "unconnected-(P9-Pad36)") (class "Default")
      (node (ref "P9") (pin "36") (pinfunction "36_36") (pintype "passive"))
    )
    (net (code "149") (name "unconnected-(R9-Pad1)") (class "Default")
      (node (ref "R9") (pin "1") (pinfunction "1_1") (pintype "passive"))
    )
    (net (code "150") (name "unconnected-(R9-Pad2)") (class "Default")
      (node (ref "R9") (pin "2") (pinfunction "2_2") (pintype "passive"))
    )
    (net (code "151") (name "unconnected-(STECKER_BOX-Pad3)") (class "Default")
      (node (ref "STECKER_BOX") (pin "3") (pinfunction "3_3") (pintype "passive"))
    )
    (net (code "152") (name "unconnected-(STECKER_BOX-Pad4)") (class "Default")
      (node (ref "STECKER_BOX") (pin "4") (pinfunction "4_4") (pintype "passive"))
    )
    (net (code "153") (name "unconnected-(U$1-VREF-Pad5)") (class "Default")
      (node (ref "U$1") (pin "5") (pinfunction "VREF_5") (pintype "output"))
    )
    (net (code "154") (name "unconnected-(U2-NC-Pad11)") (class "Default")
      (node (ref "U2") (pin "11") (pinfunction "NC_11") (pintype "no_connect"))
    )
    (net (code "155") (name "unconnected-(U2-NC_2-Pad6)") (class "Default")
      (node (ref "U2") (pin "6") (pinfunction "NC_2_6") (pintype "no_connect"))
    )
    (net (code "156") (name "unconnected-(U2-NC_3-Pad7)") (class "Default")
      (node (ref "U2") (pin "7") (pinfunction "NC_3_7") (pintype "no_connect"))
    )
    (net (code "157") (name "unconnected-(U2-VE2-Pad10)") (class "Default")
      (node (ref "U2") (pin "10") (pinfunction "VE2_10") (pintype "input"))
    )
    (net (code "158") (name "unconnected-(U4-NC-Pad11)") (class "Default")
      (node (ref "U4") (pin "11") (pinfunction "NC_11") (pintype "no_connect"))
    )
    (net (code "159") (name "unconnected-(U4-NC_2-Pad6)") (class "Default")
      (node (ref "U4") (pin "6") (pinfunction "NC_2_6") (pintype "no_connect"))
    )
    (net (code "160") (name "unconnected-(U4-NC_3-Pad7)") (class "Default")
      (node (ref "U4") (pin "7") (pinfunction "NC_3_7") (pintype "no_connect"))
    )
    (net (code "161") (name "unconnected-(U4-VE2-Pad10)") (class "Default")
      (node (ref "U4") (pin "10") (pinfunction "VE2_10") (pintype "input"))
    )
    (net (code "162") (name "~{BH_L_RESET_3V}") (class "Default")
      (node (ref "P8") (pin "8") (pinfunction "8_8") (pintype "passive"))
      (node (ref "U4") (pin "5") (pinfunction "VIC_5") (pintype "input"))
    )
    (net (code "163") (name "~{BH_L_RESET}") (class "Default")
      (node (ref "BALL-HANDLE_LEFT") (pin "4") (pinfunction "4_4") (pintype "passive"))
      (node (ref "U4") (pin "12") (pinfunction "VOC_12") (pintype "output"))
    )
    (net (code "164") (name "~{BH_R_RESET_3V}") (class "Default")
      (node (ref "P8") (pin "10") (pinfunction "10_10") (pintype "passive"))
      (node (ref "U2") (pin "5") (pinfunction "VIC_5") (pintype "input"))
    )
    (net (code "165") (name "~{BH_R_RESET}") (class "Default")
      (node (ref "BALL-HANDLE_RIGHT") (pin "4") (pinfunction "4_4") (pintype "passive"))
      (node (ref "U2") (pin "12") (pinfunction "VOC_12") (pintype "output"))
    )
  )
)
